# room_sensors.net
KiCad netlist of a schematic drawn in EAGLE
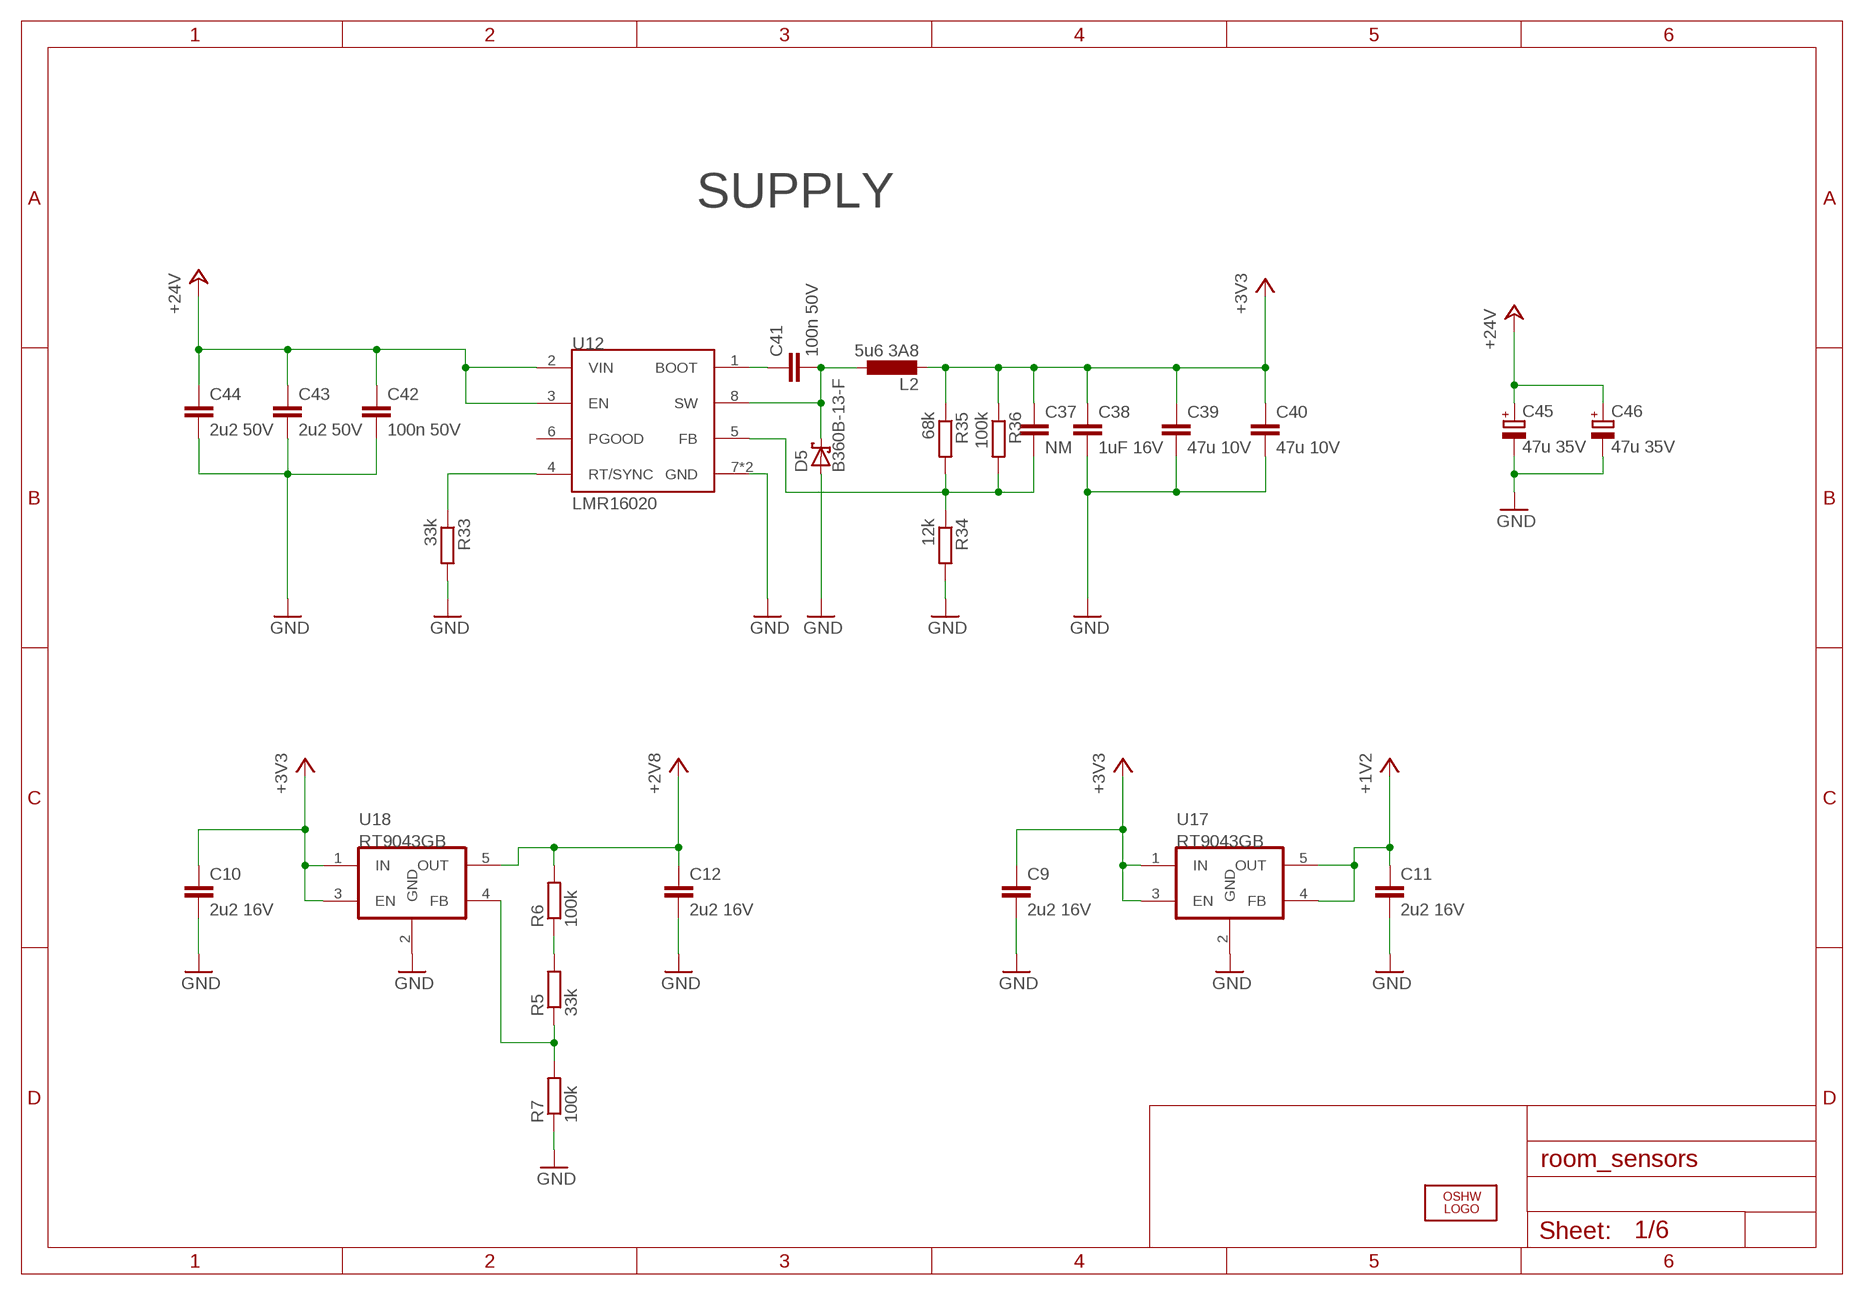
[diagram p0: schematic, sheet 1]
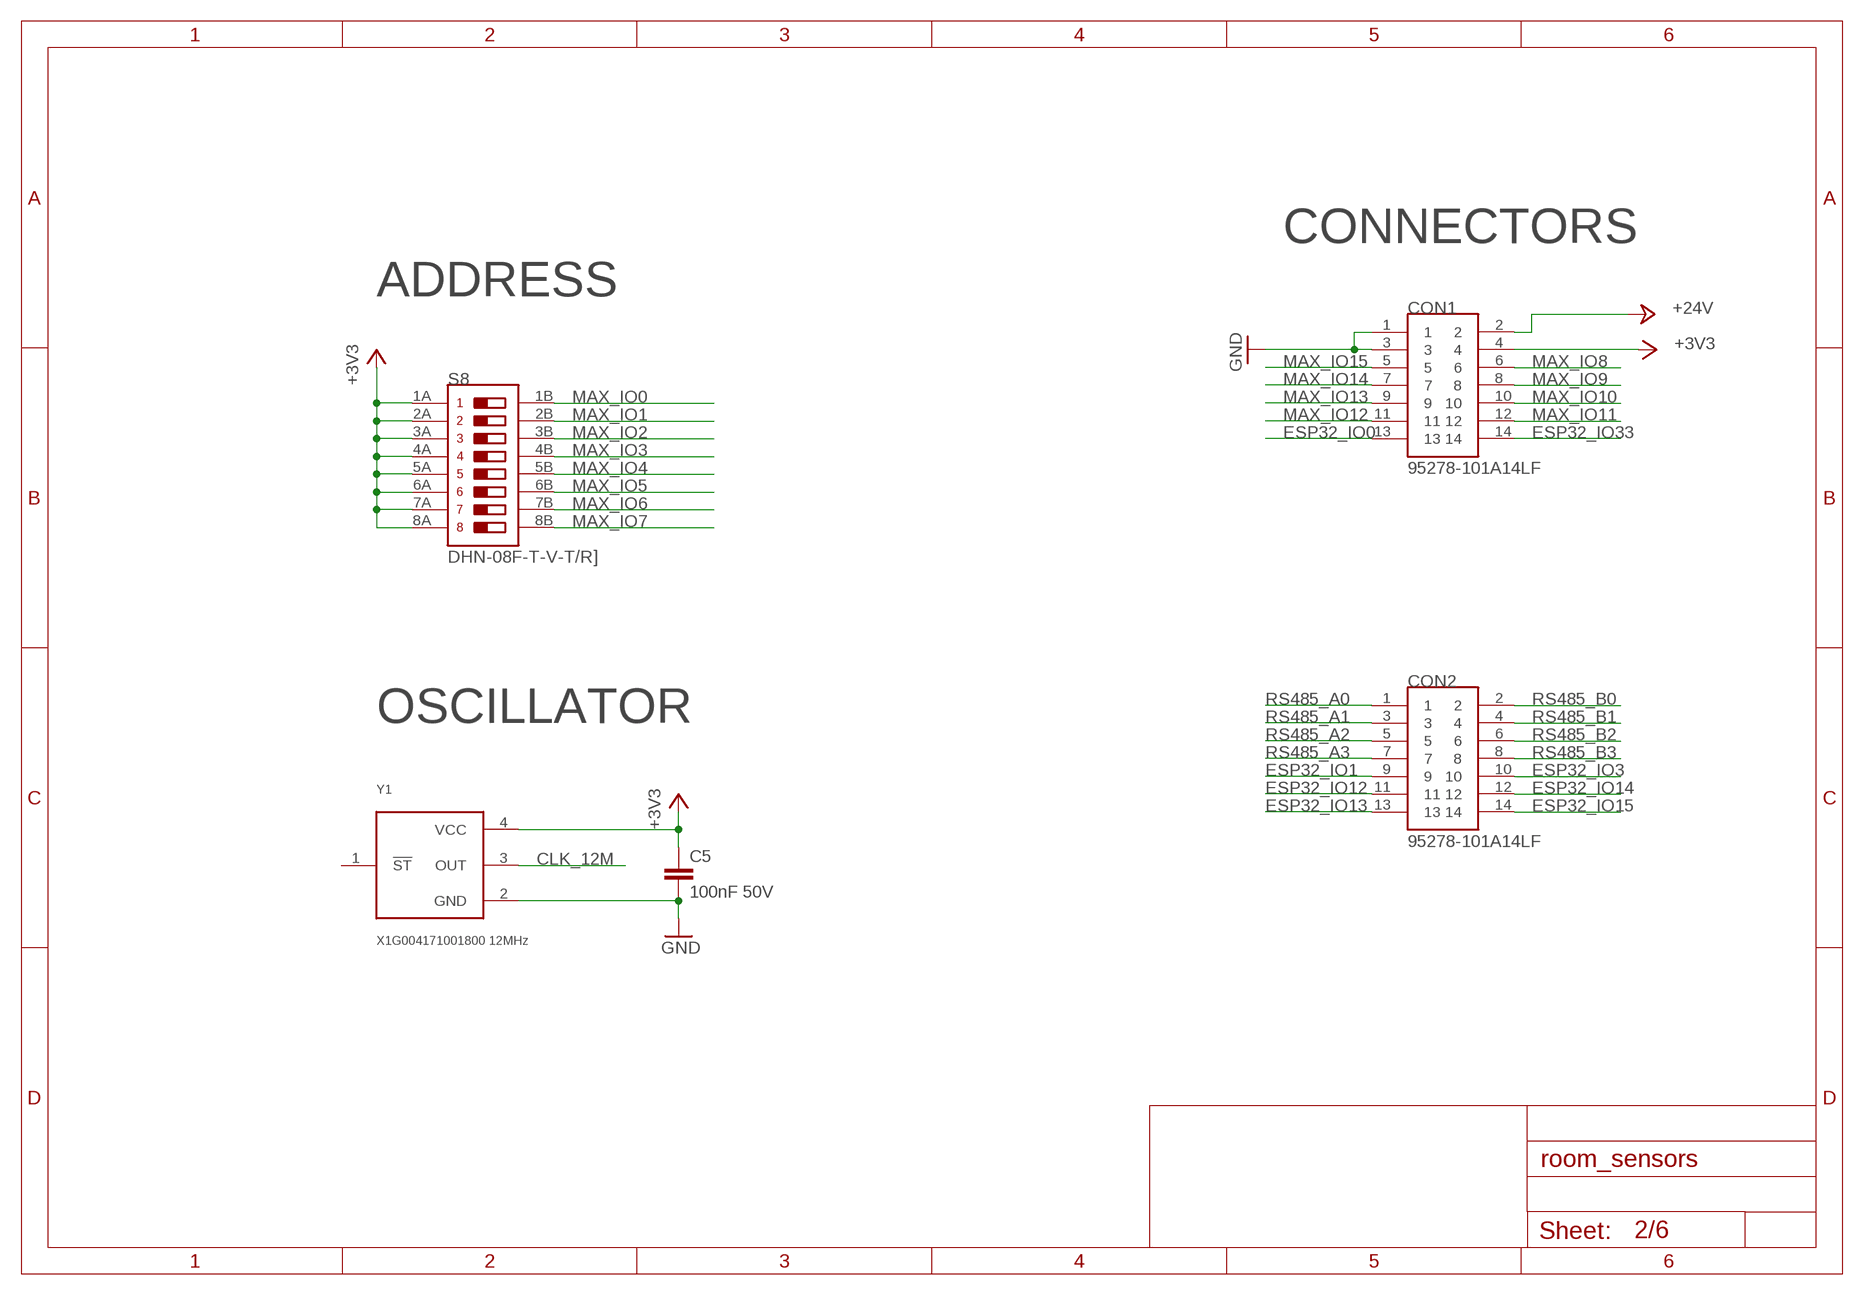
[diagram p1: schematic, sheet 2]
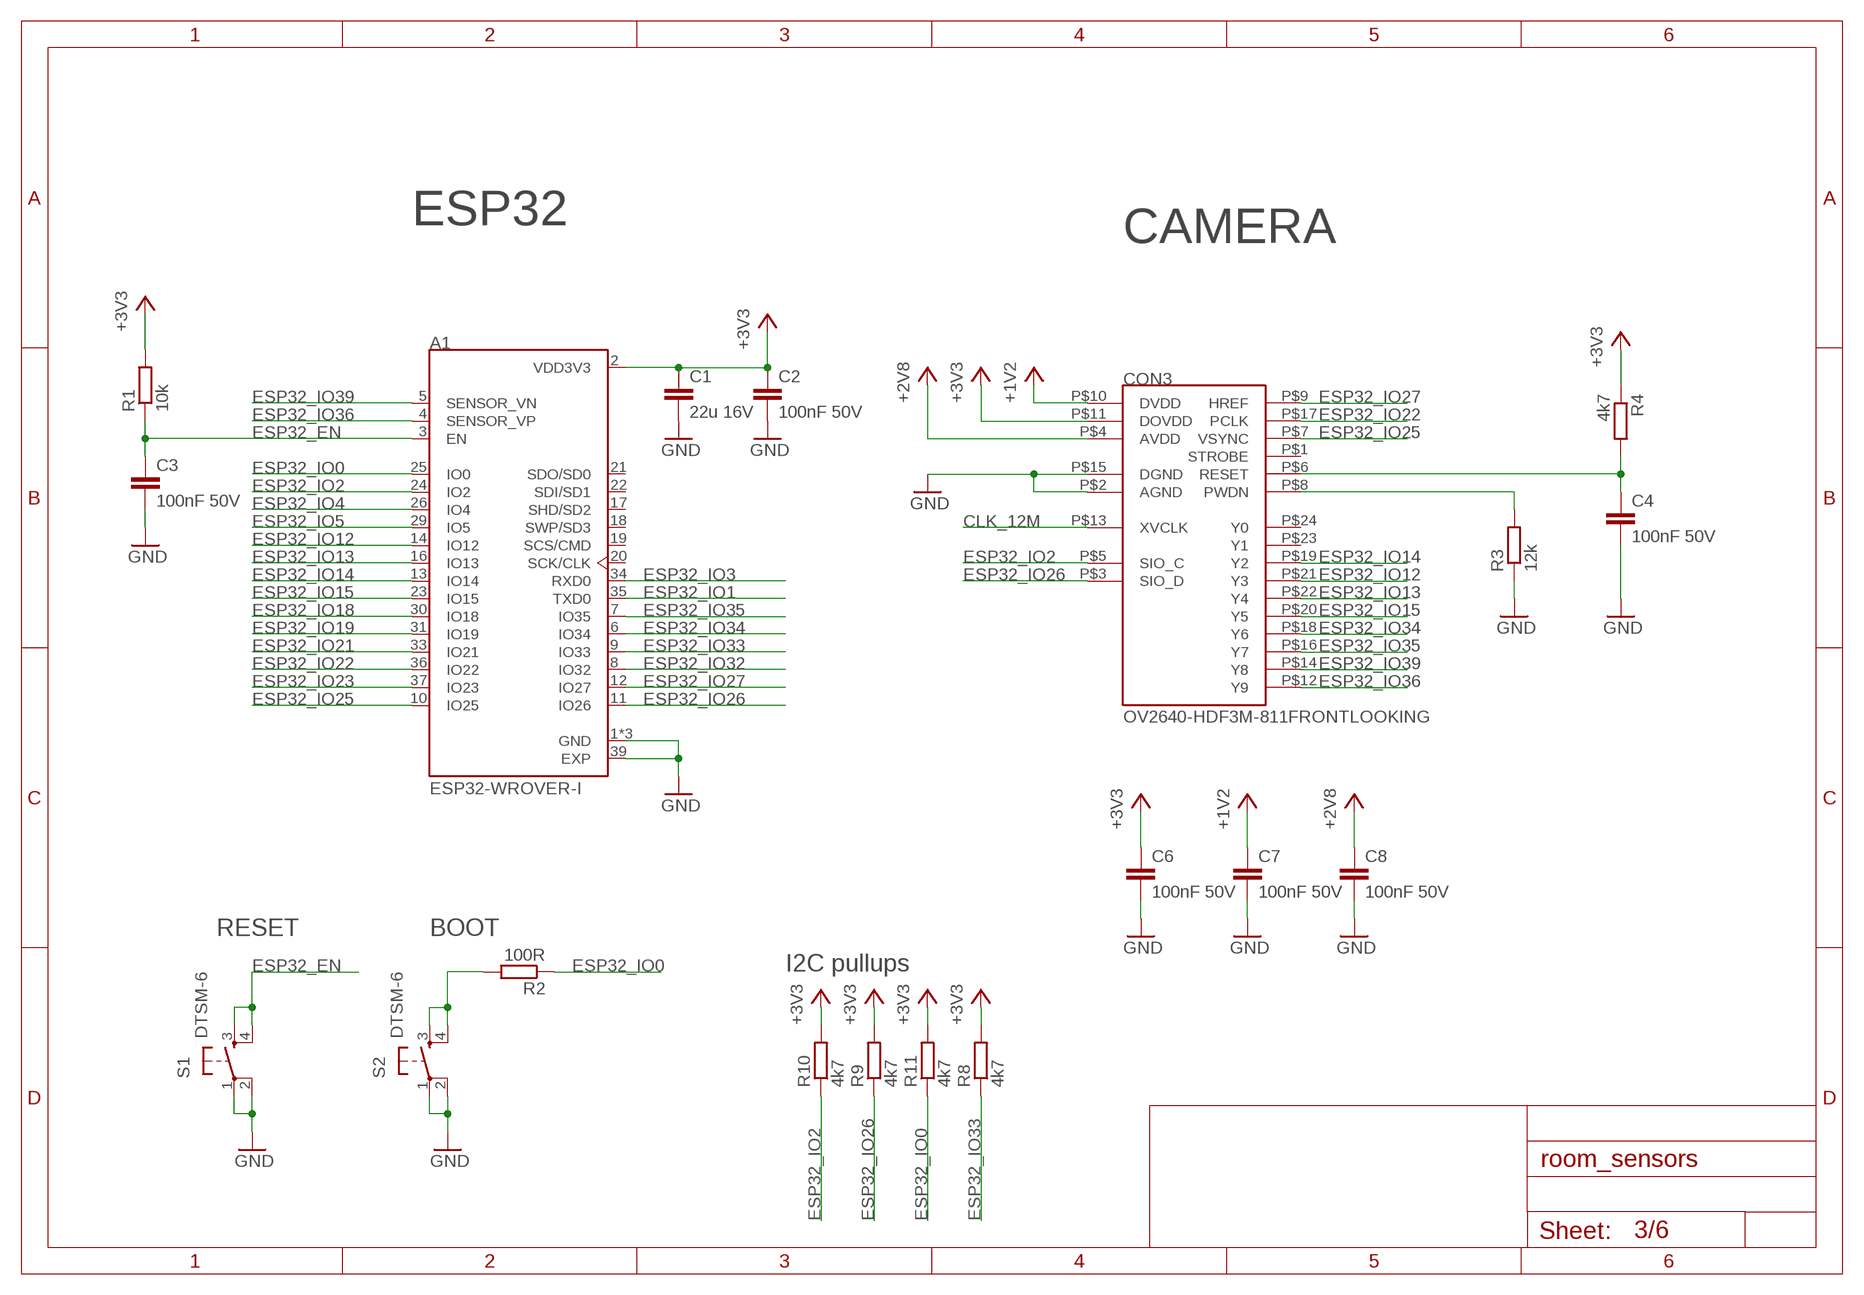
[diagram p2: schematic, sheet 3]
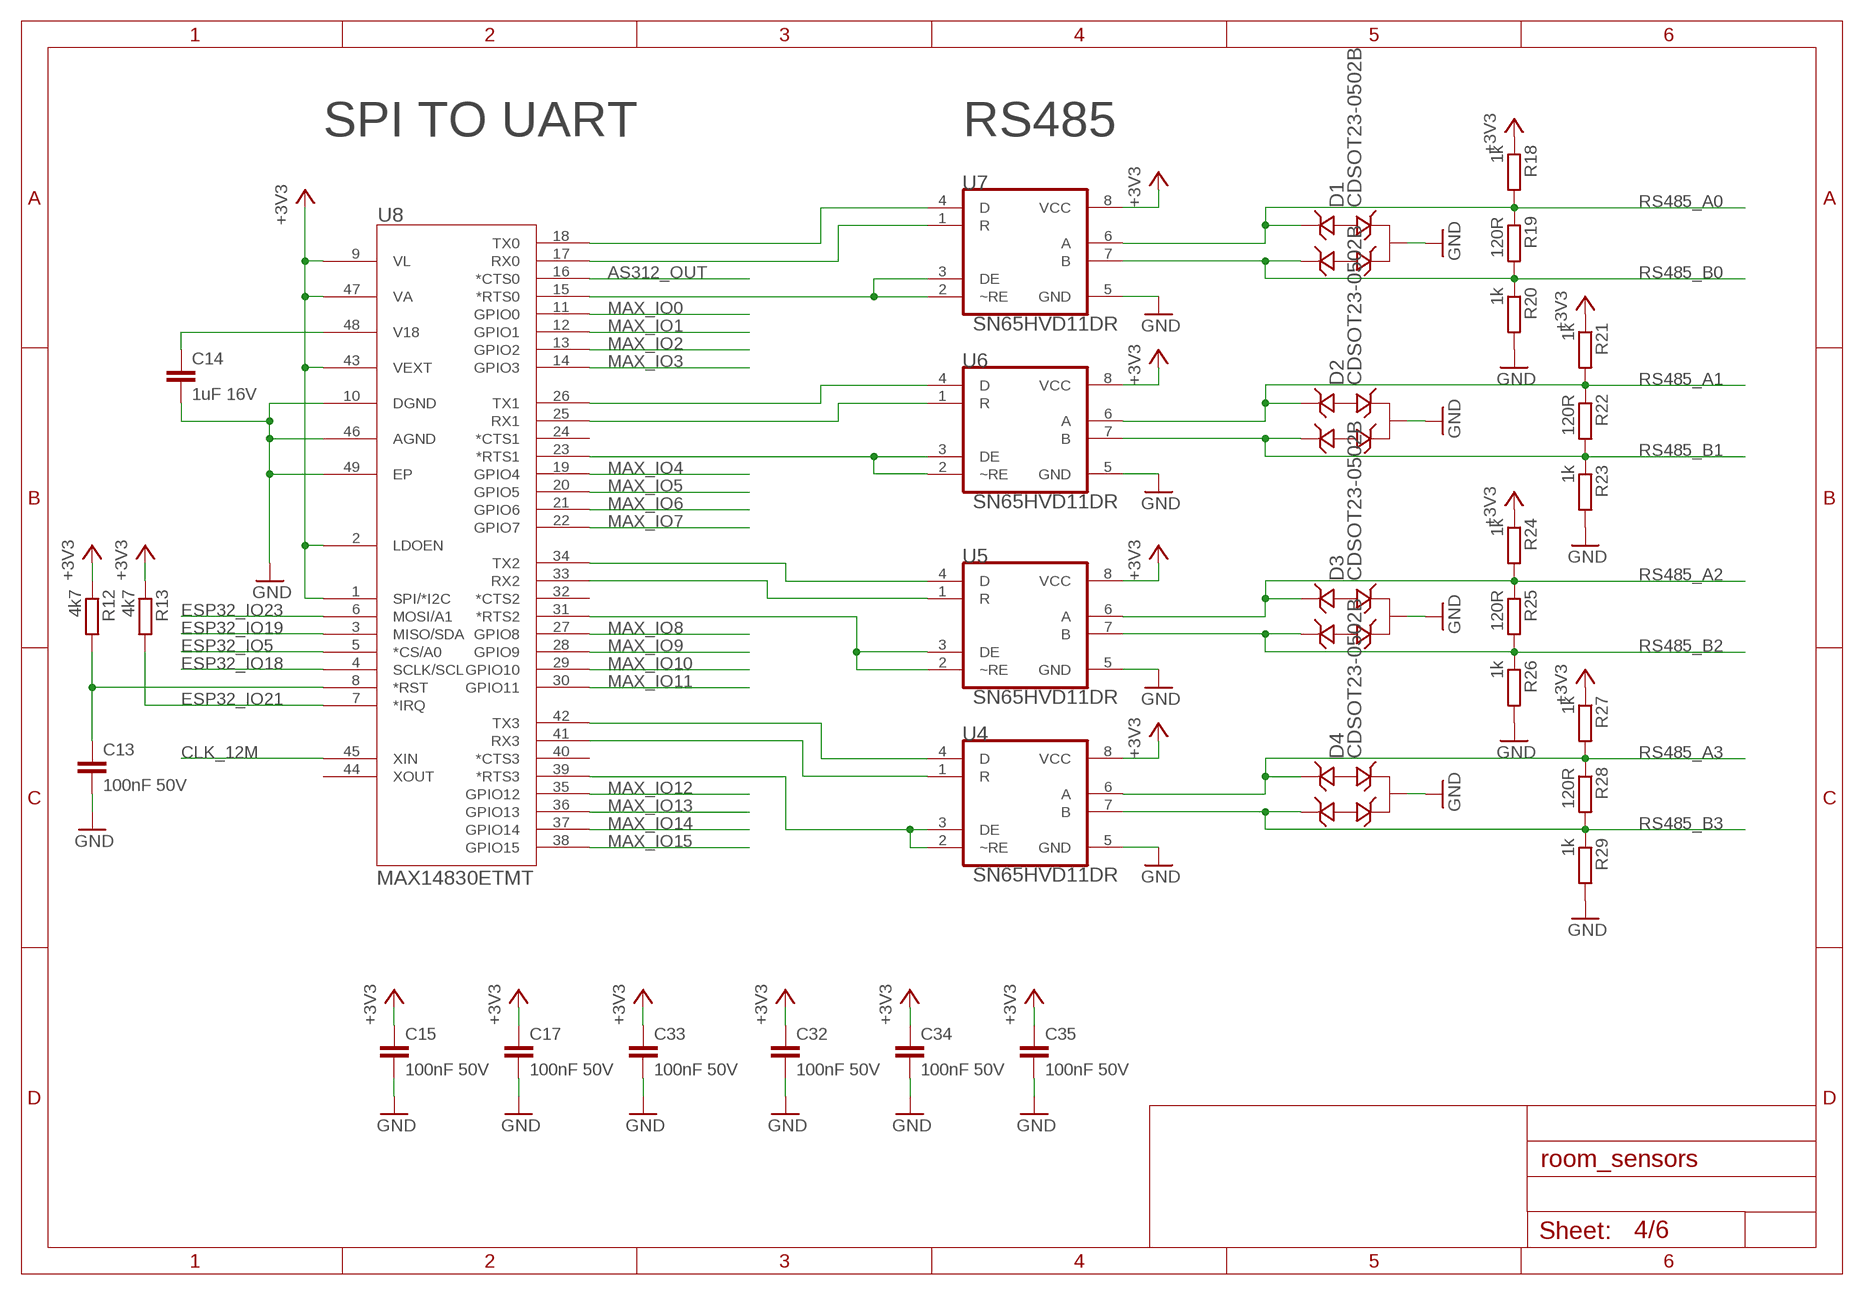
[diagram p3: schematic, sheet 4]
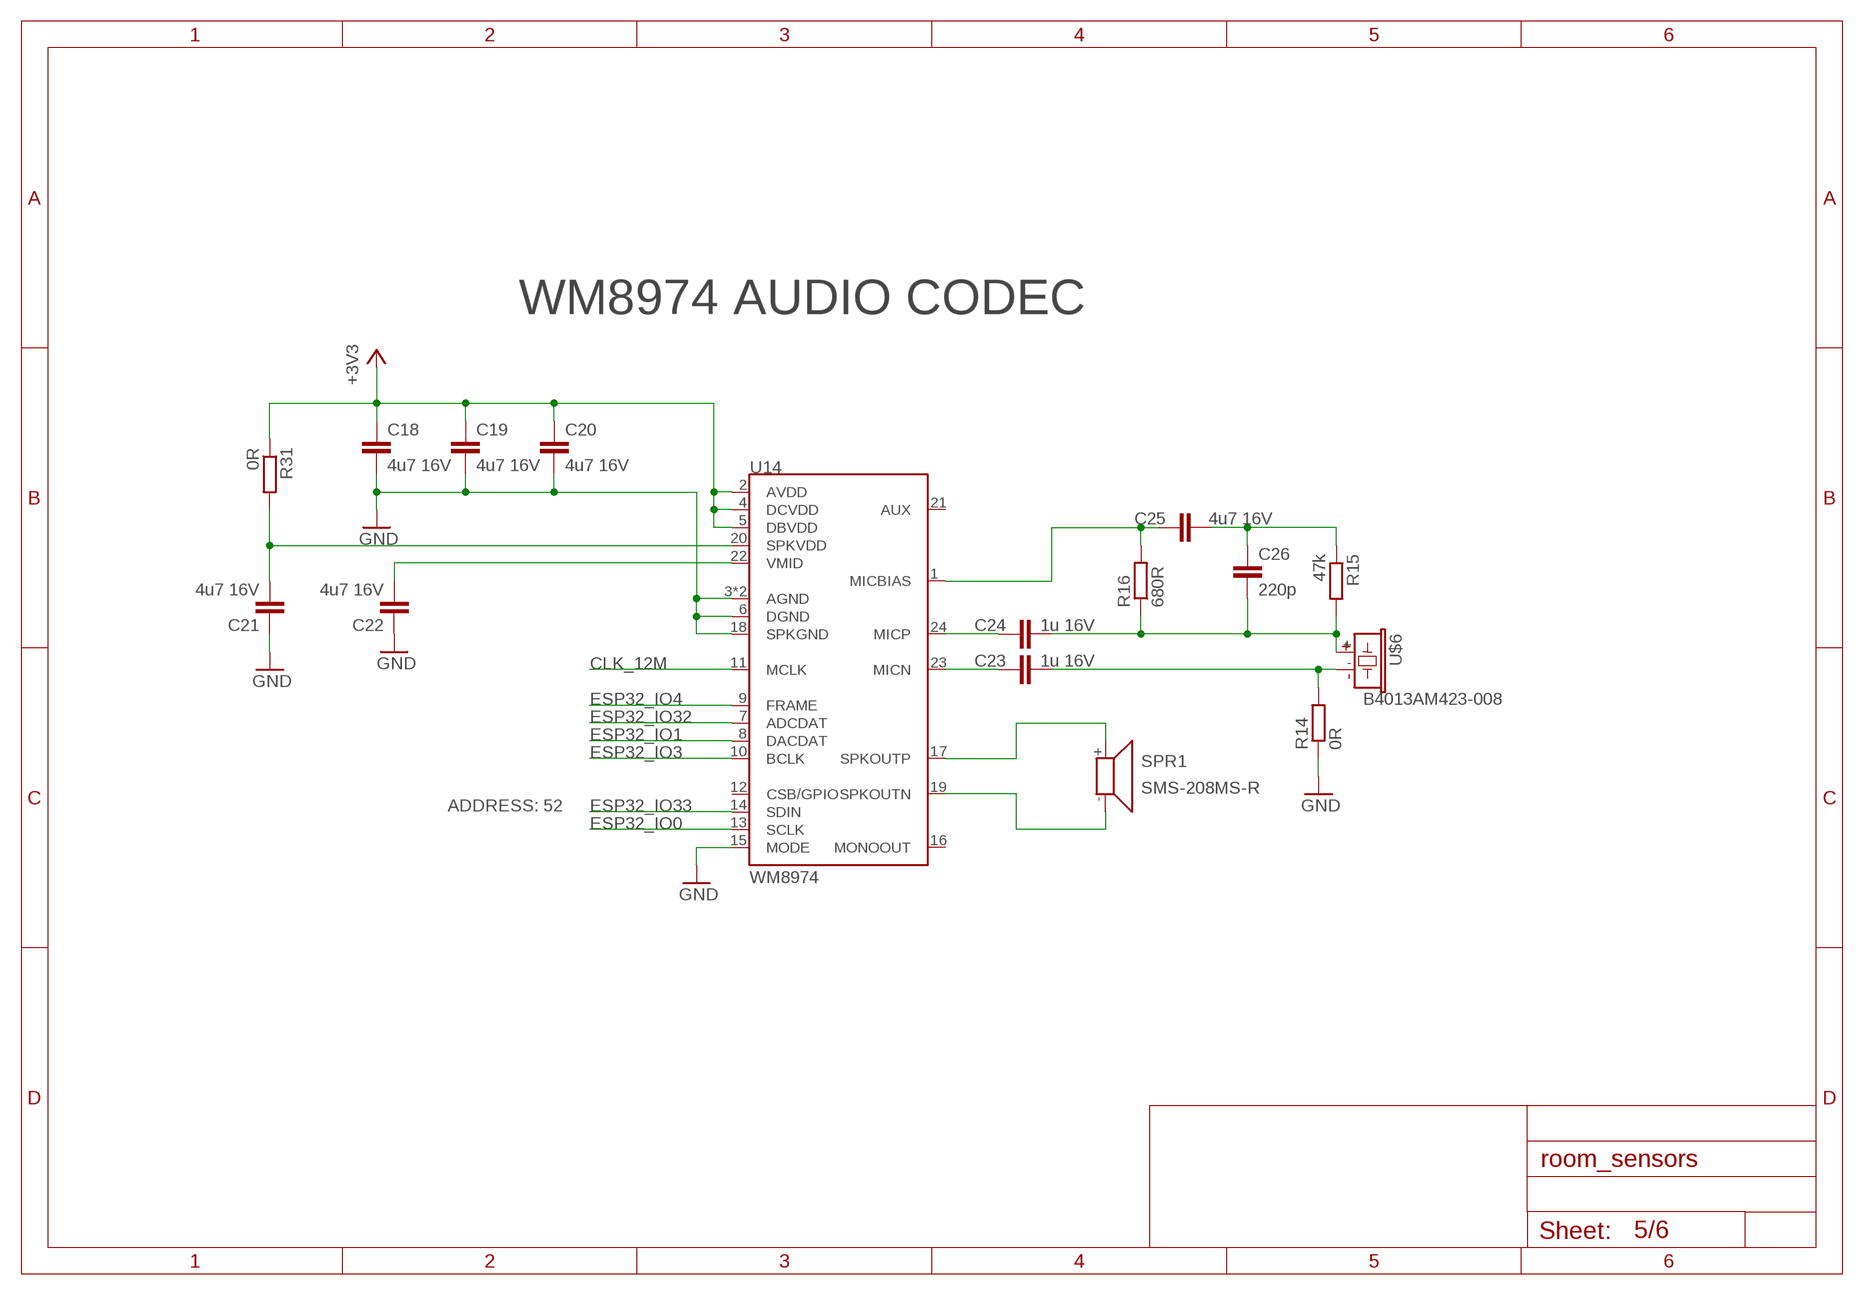
[diagram p4: schematic, sheet 5]
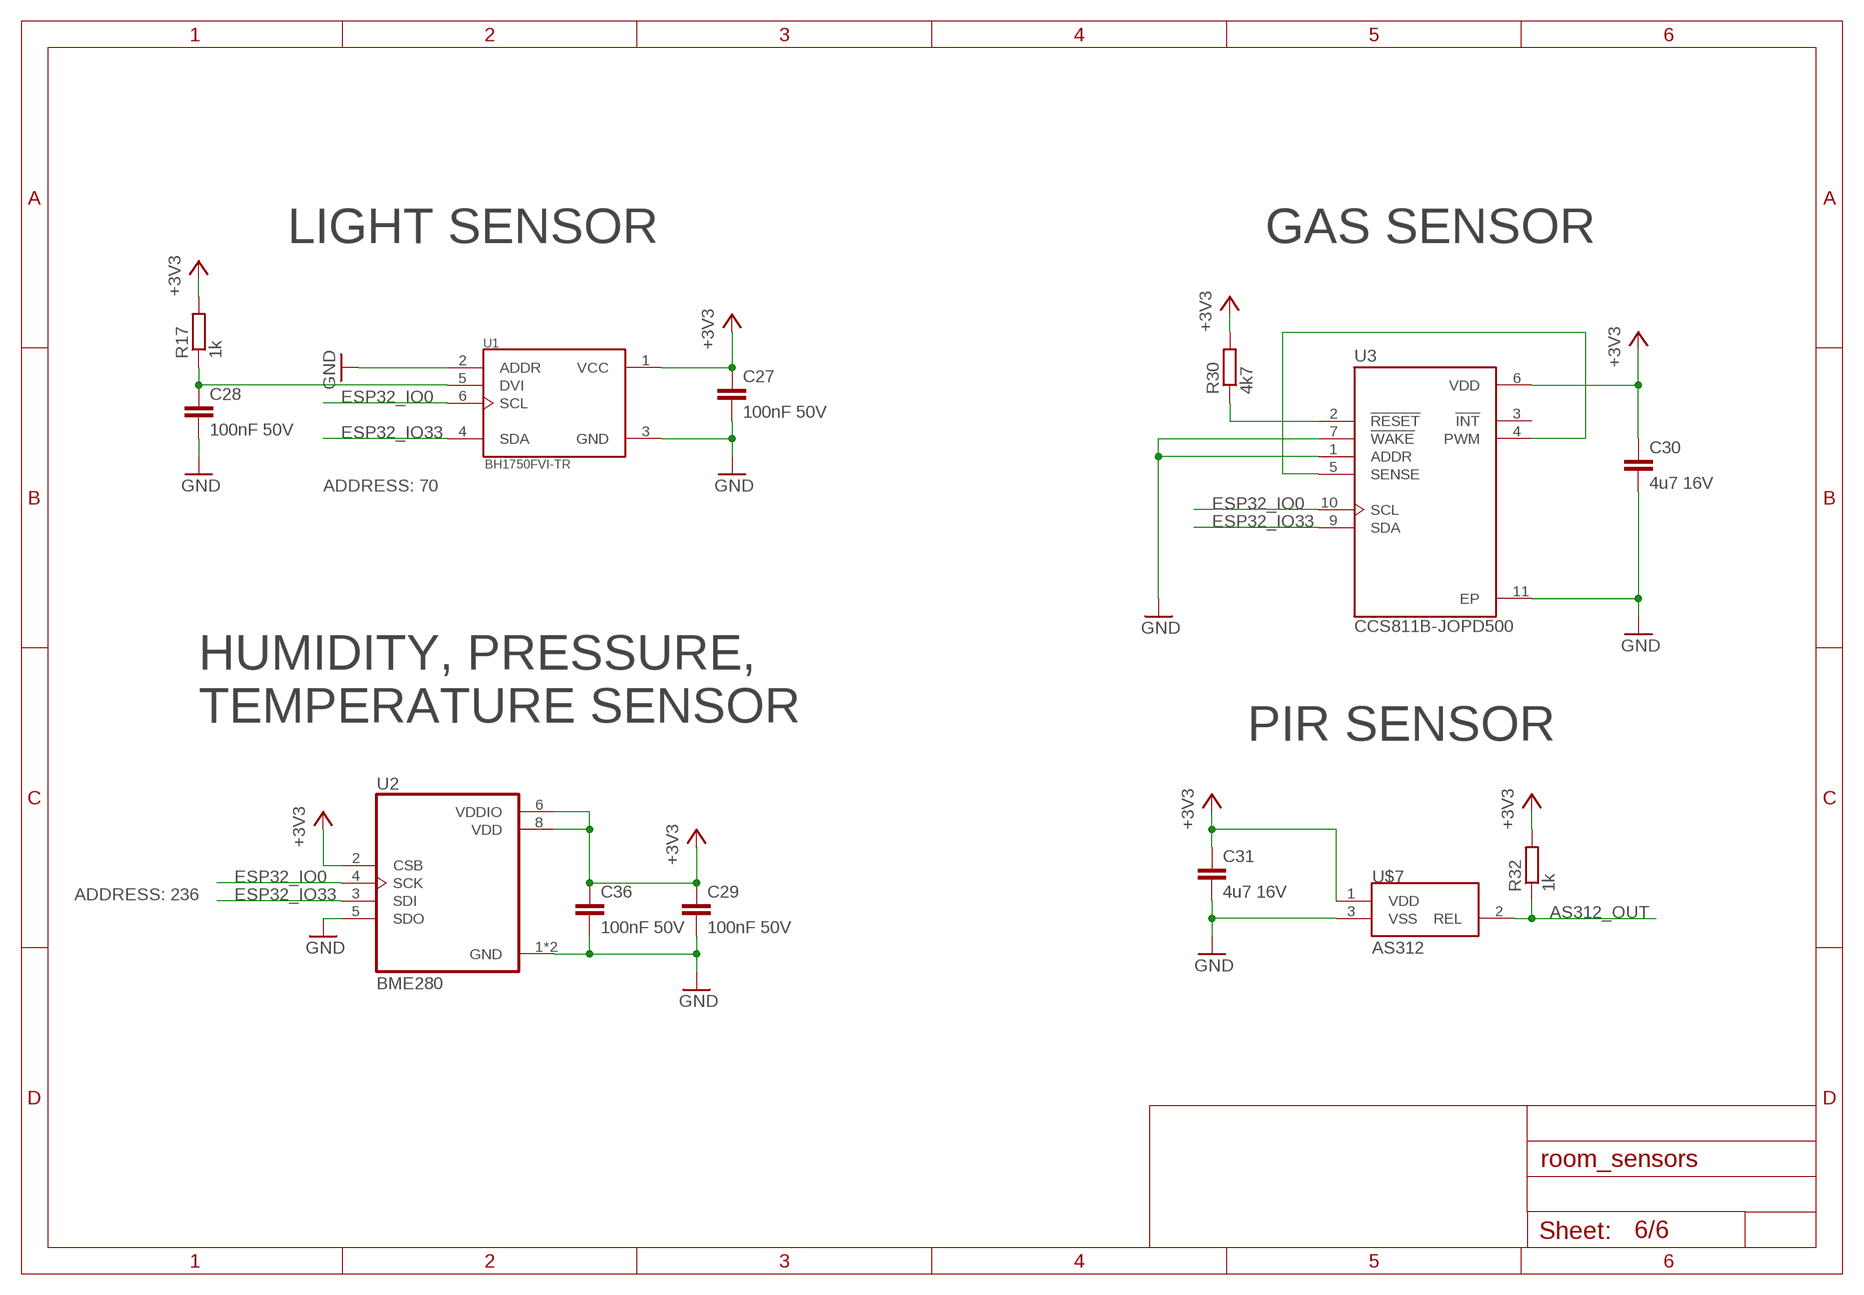
[diagram p5: schematic, sheet 6]

(export (version "E")
  (design (tool "Eeschema 10.0.6"))
  (components
    (comp (ref "C13")
      (value "100nF 50V")
      (footprint "eagle-import:C0805")
      (libsource (lib "eagle-import") (part "C-EUC0805"))
    )
    (comp (ref "C14")
      (value "1uF 16V")
      (footprint "eagle-import:C0805")
      (libsource (lib "eagle-import") (part "C-EUC0805"))
    )
    (comp (ref "C15")
      (value "100nF 50V")
      (footprint "eagle-import:C0805")
      (libsource (lib "eagle-import") (part "C-EUC0805"))
    )
    (comp (ref "C17")
      (value "100nF 50V")
      (footprint "eagle-import:C0805")
      (libsource (lib "eagle-import") (part "C-EUC0805"))
    )
    (comp (ref "C32")
      (value "100nF 50V")
      (footprint "eagle-import:C0805")
      (libsource (lib "eagle-import") (part "C-EUC0805"))
    )
    (comp (ref "C33")
      (value "100nF 50V")
      (footprint "eagle-import:C0805")
      (libsource (lib "eagle-import") (part "C-EUC0805"))
    )
    (comp (ref "C34")
      (value "100nF 50V")
      (footprint "eagle-import:C0805")
      (libsource (lib "eagle-import") (part "C-EUC0805"))
    )
    (comp (ref "C35")
      (value "100nF 50V")
      (footprint "eagle-import:C0805")
      (libsource (lib "eagle-import") (part "C-EUC0805"))
    )
    (comp (ref "D1")
      (value "CDSOT23-0502B")
      (footprint "eagle-import:SOT-23-3")
      (fields (field (name "MF") "Bourns") (field (name "MP") "CDSOT23-SM712"))
      (libsource (lib "eagle-import") (part "CDSOT23-SM712"))
    )
    (comp (ref "D2")
      (value "CDSOT23-0502B")
      (footprint "eagle-import:SOT-23-3")
      (fields (field (name "MF") "Bourns") (field (name "MP") "CDSOT23-SM712"))
      (libsource (lib "eagle-import") (part "CDSOT23-SM712"))
    )
    (comp (ref "D3")
      (value "CDSOT23-0502B")
      (footprint "eagle-import:SOT-23-3")
      (fields (field (name "MF") "Bourns") (field (name "MP") "CDSOT23-SM712"))
      (libsource (lib "eagle-import") (part "CDSOT23-SM712"))
    )
    (comp (ref "D4")
      (value "CDSOT23-0502B")
      (footprint "eagle-import:SOT-23-3")
      (fields (field (name "MF") "Bourns") (field (name "MP") "CDSOT23-SM712"))
      (libsource (lib "eagle-import") (part "CDSOT23-SM712"))
    )
    (comp (ref "R12")
      (value "4k7")
      (footprint "eagle-import:R1206")
      (libsource (lib "eagle-import") (part "R-EU_R1206"))
    )
    (comp (ref "R13")
      (value "4k7")
      (footprint "eagle-import:R1206")
      (libsource (lib "eagle-import") (part "R-EU_R1206"))
    )
    (comp (ref "R18")
      (value "1k")
      (footprint "eagle-import:R1206")
      (libsource (lib "eagle-import") (part "R-EU_R1206"))
    )
    (comp (ref "R19")
      (value "120R")
      (footprint "eagle-import:R1206")
      (libsource (lib "eagle-import") (part "R-EU_R1206"))
    )
    (comp (ref "R20")
      (value "1k")
      (footprint "eagle-import:R1206")
      (libsource (lib "eagle-import") (part "R-EU_R1206"))
    )
    (comp (ref "R21")
      (value "1k")
      (footprint "eagle-import:R1206")
      (libsource (lib "eagle-import") (part "R-EU_R1206"))
    )
    (comp (ref "R22")
      (value "120R")
      (footprint "eagle-import:R1206")
      (libsource (lib "eagle-import") (part "R-EU_R1206"))
    )
    (comp (ref "R23")
      (value "1k")
      (footprint "eagle-import:R1206")
      (libsource (lib "eagle-import") (part "R-EU_R1206"))
    )
    (comp (ref "R24")
      (value "1k")
      (footprint "eagle-import:R1206")
      (libsource (lib "eagle-import") (part "R-EU_R1206"))
    )
    (comp (ref "R25")
      (value "120R")
      (footprint "eagle-import:R1206")
      (libsource (lib "eagle-import") (part "R-EU_R1206"))
    )
    (comp (ref "R26")
      (value "1k")
      (footprint "eagle-import:R1206")
      (libsource (lib "eagle-import") (part "R-EU_R1206"))
    )
    (comp (ref "R27")
      (value "1k")
      (footprint "eagle-import:R1206")
      (libsource (lib "eagle-import") (part "R-EU_R1206"))
    )
    (comp (ref "R28")
      (value "120R")
      (footprint "eagle-import:R1206")
      (libsource (lib "eagle-import") (part "R-EU_R1206"))
    )
    (comp (ref "R29")
      (value "1k")
      (footprint "eagle-import:R1206")
      (libsource (lib "eagle-import") (part "R-EU_R1206"))
    )
    (comp (ref "U4")
      (value "SN65HVD11DR")
      (footprint "eagle-import:SOIC127P600X175-8N")
      (fields (field (name "MF") "Texas Instruments"))
      (libsource (lib "eagle-import") (part "SN65HVD11DR"))
    )
    (comp (ref "U5")
      (value "SN65HVD11DR")
      (footprint "eagle-import:SOIC127P600X175-8N")
      (fields (field (name "MF") "Texas Instruments"))
      (libsource (lib "eagle-import") (part "SN65HVD11DR"))
    )
    (comp (ref "U6")
      (value "SN65HVD11DR")
      (footprint "eagle-import:SOIC127P600X175-8N")
      (fields (field (name "MF") "Texas Instruments"))
      (libsource (lib "eagle-import") (part "SN65HVD11DR"))
    )
    (comp (ref "U7")
      (value "SN65HVD11DR")
      (footprint "eagle-import:SOIC127P600X175-8N")
      (fields (field (name "MF") "Texas Instruments"))
      (libsource (lib "eagle-import") (part "SN65HVD11DR"))
    )
    (comp (ref "U8")
      (value "MAX14830ETMT")
      (footprint "eagle-import:21-0144H_T4877-3")
      (fields (field (name "MF") "Maxim Integrated") (field (name "MP") "MAX14830ETM+"))
      (libsource (lib "eagle-import") (part "MAX14830ETMT"))
    )
    (comp (ref "C5")
      (value "100nF 50V")
      (footprint "eagle-import:C0805")
      (libsource (lib "eagle-import") (part "C-EUC0805"))
    )
    (comp (ref "CON1")
      (value "95278-101A14LF")
      (footprint "eagle-import:95278-101A14LF")
      (libsource (lib "eagle-import") (part "95278-101A14LF"))
    )
    (comp (ref "CON2")
      (value "95278-101A14LF")
      (footprint "eagle-import:95278-101A14LF")
      (libsource (lib "eagle-import") (part "95278-101A14LF"))
    )
    (comp (ref "S8")
      (value "DHN-08F-T-V-T/R]")
      (footprint "eagle-import:DHN-08F-T-V-T_R]")
      (libsource (lib "eagle-import") (part "DHN-08F-T-V-T/R]"))
    )
    (comp (ref "Y1")
      (value "X1G004171001800 12MHz")
      (footprint "eagle-import:OSCCC250X200X80-4N")
      (fields (field (name "MF") "EPSON") (field (name "MP") "X1G0041710033"))
      (libsource (lib "eagle-import") (part "X1G0041710033"))
    )
    (comp (ref "C18")
      (value "4u7 16V")
      (footprint "eagle-import:C0805")
      (libsource (lib "eagle-import") (part "C-EUC0805"))
    )
    (comp (ref "C19")
      (value "4u7 16V")
      (footprint "eagle-import:C0805")
      (libsource (lib "eagle-import") (part "C-EUC0805"))
    )
    (comp (ref "C20")
      (value "4u7 16V")
      (footprint "eagle-import:C0805")
      (libsource (lib "eagle-import") (part "C-EUC0805"))
    )
    (comp (ref "C21")
      (value "4u7 16V")
      (footprint "eagle-import:C0805")
      (libsource (lib "eagle-import") (part "C-EUC0805"))
    )
    (comp (ref "C22")
      (value "4u7 16V")
      (footprint "eagle-import:C0805")
      (libsource (lib "eagle-import") (part "C-EUC0805"))
    )
    (comp (ref "C23")
      (value "1u 16V")
      (footprint "eagle-import:C0805")
      (libsource (lib "eagle-import") (part "C-EUC0805"))
    )
    (comp (ref "C24")
      (value "1u 16V")
      (footprint "eagle-import:C0805")
      (libsource (lib "eagle-import") (part "C-EUC0805"))
    )
    (comp (ref "C25")
      (value "4u7 16V")
      (footprint "eagle-import:C0805")
      (libsource (lib "eagle-import") (part "C-EUC0805"))
    )
    (comp (ref "C26")
      (value "220p")
      (footprint "eagle-import:C0805")
      (libsource (lib "eagle-import") (part "C-EUC0805"))
    )
    (comp (ref "R14")
      (value "0R")
      (footprint "eagle-import:R1206")
      (libsource (lib "eagle-import") (part "R-EU_R1206"))
    )
    (comp (ref "R15")
      (value "47k")
      (footprint "eagle-import:R1206")
      (libsource (lib "eagle-import") (part "R-EU_R1206"))
    )
    (comp (ref "R16")
      (value "680R")
      (footprint "eagle-import:R1206")
      (libsource (lib "eagle-import") (part "R-EU_R1206"))
    )
    (comp (ref "R31")
      (value "0R")
      (footprint "eagle-import:R0603")
      (libsource (lib "eagle-import") (part "R-EU_R0603"))
    )
    (comp (ref "SPR1")
      (value "SMS-208MS-R")
      (footprint "eagle-import:SMS-2008MS-R")
      (libsource (lib "eagle-import") (part "SMS-208MS-R"))
    )
    (comp (ref "U$6")
      (value "B4013AM423-008")
      (footprint "eagle-import:MIC")
      (libsource (lib "eagle-import") (part "B4013AM423-008"))
    )
    (comp (ref "U14")
      (value "WM8974")
      (footprint "eagle-import:QFN-24_ALT2")
      (libsource (lib "eagle-import") (part "WM8974"))
    )
    (comp (ref "C9")
      (value "2u2 16V")
      (footprint "eagle-import:C1206")
      (libsource (lib "eagle-import") (part "C-EUC1206"))
    )
    (comp (ref "C10")
      (value "2u2 16V")
      (footprint "eagle-import:C1206")
      (libsource (lib "eagle-import") (part "C-EUC1206"))
    )
    (comp (ref "C11")
      (value "2u2 16V")
      (footprint "eagle-import:C1206")
      (libsource (lib "eagle-import") (part "C-EUC1206"))
    )
    (comp (ref "C12")
      (value "2u2 16V")
      (footprint "eagle-import:C1206")
      (libsource (lib "eagle-import") (part "C-EUC1206"))
    )
    (comp (ref "C37")
      (value "NM")
      (footprint "eagle-import:C0805")
      (libsource (lib "eagle-import") (part "C-EUC0805"))
    )
    (comp (ref "C38")
      (value "1uF 16V")
      (footprint "eagle-import:C0805")
      (libsource (lib "eagle-import") (part "C-EUC0805"))
    )
    (comp (ref "C39")
      (value "47u 10V")
      (footprint "eagle-import:C1210")
      (libsource (lib "eagle-import") (part "C-EUC1210"))
    )
    (comp (ref "C40")
      (value "47u 10V")
      (footprint "eagle-import:C1210")
      (libsource (lib "eagle-import") (part "C-EUC1210"))
    )
    (comp (ref "C41")
      (value "100n 50V")
      (footprint "eagle-import:C1206")
      (libsource (lib "eagle-import") (part "C-EUC1206"))
    )
    (comp (ref "C42")
      (value "100n 50V")
      (footprint "eagle-import:C1206")
      (libsource (lib "eagle-import") (part "C-EUC1206"))
    )
    (comp (ref "C43")
      (value "2u2 50V")
      (footprint "eagle-import:C1206")
      (libsource (lib "eagle-import") (part "C-EUC1206"))
    )
    (comp (ref "C44")
      (value "2u2 50V")
      (footprint "eagle-import:C1206")
      (libsource (lib "eagle-import") (part "C-EUC1206"))
    )
    (comp (ref "C45")
      (value "47u 35V")
      (footprint "eagle-import:UD-5X5,8_NICHICON")
      (libsource (lib "eagle-import") (part "CPOL-EUUD-5X5,8"))
    )
    (comp (ref "C46")
      (value "47u 35V")
      (footprint "eagle-import:UD-5X5,8_NICHICON")
      (libsource (lib "eagle-import") (part "CPOL-EUUD-5X5,8"))
    )
    (comp (ref "D5")
      (value "B360B-13-F")
      (footprint "eagle-import:SMB")
      (libsource (lib "eagle-import") (part "MBRS130LT3"))
    )
    (comp (ref "L2")
      (value "5u6 3A8")
      (footprint "eagle-import:SLF10145T-150M2R2-PF")
      (libsource (lib "eagle-import") (part "SLF10145T-150M2R2-PF"))
    )
    (comp (ref "LOGO1")
      (value "OSHW_LOGO_FILLX0350-NT")
      (footprint "eagle-import:OSHW_FILLX350_NOTEXT")
      (libsource (lib "eagle-import") (part "OSHW_LOGO_FILLX0350-NT"))
    )
    (comp (ref "R5")
      (value "33k")
      (footprint "eagle-import:R1206")
      (libsource (lib "eagle-import") (part "R-EU_R1206"))
    )
    (comp (ref "R6")
      (value "100k")
      (footprint "eagle-import:R1206")
      (libsource (lib "eagle-import") (part "R-EU_R1206"))
    )
    (comp (ref "R7")
      (value "100k")
      (footprint "eagle-import:R1206")
      (libsource (lib "eagle-import") (part "R-EU_R1206"))
    )
    (comp (ref "R33")
      (value "33k")
      (footprint "eagle-import:R1206")
      (libsource (lib "eagle-import") (part "R-EU_R1206"))
    )
    (comp (ref "R34")
      (value "12k")
      (footprint "eagle-import:R1206")
      (libsource (lib "eagle-import") (part "R-EU_R1206"))
    )
    (comp (ref "R35")
      (value "68k")
      (footprint "eagle-import:R1206")
      (libsource (lib "eagle-import") (part "R-EU_R1206"))
    )
    (comp (ref "R36")
      (value "100k")
      (footprint "eagle-import:R1206")
      (libsource (lib "eagle-import") (part "R-EU_R1206"))
    )
    (comp (ref "U12")
      (value "LMR16020")
      (footprint "eagle-import:SOIC127P600X170-8N")
      (libsource (lib "eagle-import") (part "LMR16020"))
    )
    (comp (ref "U17")
      (value "RT9043GB")
      (footprint "eagle-import:SOP95P275X110-5N")
      (libsource (lib "eagle-import") (part "RT9043GB"))
    )
    (comp (ref "U18")
      (value "RT9043GB")
      (footprint "eagle-import:SOP95P275X110-5N")
      (libsource (lib "eagle-import") (part "RT9043GB"))
    )
    (comp (ref "A1")
      (value "ESP32-WROVER-I")
      (footprint "eagle-import:XCVR_ESP32-WROVER-I")
      (fields (field (name "MF") "Espressif Systems"))
      (libsource (lib "eagle-import") (part "ESP32-WROVER-I"))
    )
    (comp (ref "C1")
      (value "22u 16V")
      (footprint "eagle-import:C1210")
      (libsource (lib "eagle-import") (part "C-EUC1210"))
    )
    (comp (ref "C2")
      (value "100nF 50V")
      (footprint "eagle-import:C0805")
      (libsource (lib "eagle-import") (part "C-EUC0805"))
    )
    (comp (ref "C3")
      (value "100nF 50V")
      (footprint "eagle-import:C0805")
      (libsource (lib "eagle-import") (part "C-EUC0805"))
    )
    (comp (ref "C4")
      (value "100nF 50V")
      (footprint "eagle-import:C0805")
      (libsource (lib "eagle-import") (part "C-EUC0805"))
    )
    (comp (ref "C6")
      (value "100nF 50V")
      (footprint "eagle-import:C0805")
      (libsource (lib "eagle-import") (part "C-EUC0805"))
    )
    (comp (ref "C7")
      (value "100nF 50V")
      (footprint "eagle-import:C0805")
      (libsource (lib "eagle-import") (part "C-EUC0805"))
    )
    (comp (ref "C8")
      (value "100nF 50V")
      (footprint "eagle-import:C0805")
      (libsource (lib "eagle-import") (part "C-EUC0805"))
    )
    (comp (ref "CON3")
      (value "OV2640-HDF3M-811FRONTLOOKING")
      (footprint "eagle-import:FH34SRJ-24S-0.5SH(50)")
      (libsource (lib "eagle-import") (part "OV2640-HDF3M-811FRONTLOOKING"))
    )
    (comp (ref "R1")
      (value "10k")
      (footprint "eagle-import:R1206")
      (libsource (lib "eagle-import") (part "R-EU_R1206"))
    )
    (comp (ref "R2")
      (value "100R")
      (footprint "eagle-import:R1206")
      (libsource (lib "eagle-import") (part "R-EU_R1206"))
    )
    (comp (ref "R3")
      (value "12k")
      (footprint "eagle-import:R1206")
      (libsource (lib "eagle-import") (part "R-EU_R1206"))
    )
    (comp (ref "R4")
      (value "4k7")
      (footprint "eagle-import:R1206")
      (libsource (lib "eagle-import") (part "R-EU_R1206"))
    )
    (comp (ref "R8")
      (value "4k7")
      (footprint "eagle-import:R1206")
      (libsource (lib "eagle-import") (part "R-EU_R1206"))
    )
    (comp (ref "R9")
      (value "4k7")
      (footprint "eagle-import:R1206")
      (libsource (lib "eagle-import") (part "R-EU_R1206"))
    )
    (comp (ref "R10")
      (value "4k7")
      (footprint "eagle-import:R1206")
      (libsource (lib "eagle-import") (part "R-EU_R1206"))
    )
    (comp (ref "R11")
      (value "4k7")
      (footprint "eagle-import:R1206")
      (libsource (lib "eagle-import") (part "R-EU_R1206"))
    )
    (comp (ref "S1")
      (value "DTSM-6")
      (footprint "eagle-import:DTSM-6")
      (libsource (lib "eagle-import") (part "DTSM-6"))
    )
    (comp (ref "S2")
      (value "DTSM-6")
      (footprint "eagle-import:DTSM-6")
      (libsource (lib "eagle-import") (part "DTSM-6"))
    )
    (comp (ref "C27")
      (value "100nF 50V")
      (footprint "eagle-import:C0805")
      (libsource (lib "eagle-import") (part "C-EUC0805"))
    )
    (comp (ref "C28")
      (value "100nF 50V")
      (footprint "eagle-import:C0805")
      (libsource (lib "eagle-import") (part "C-EUC0805"))
    )
    (comp (ref "C29")
      (value "100nF 50V")
      (footprint "eagle-import:C0805")
      (libsource (lib "eagle-import") (part "C-EUC0805"))
    )
    (comp (ref "C30")
      (value "4u7 16V")
      (footprint "eagle-import:C0805")
      (libsource (lib "eagle-import") (part "C-EUC0805"))
    )
    (comp (ref "C31")
      (value "4u7 16V")
      (footprint "eagle-import:C0805")
      (libsource (lib "eagle-import") (part "C-EUC0805"))
    )
    (comp (ref "C36")
      (value "100nF 50V")
      (footprint "eagle-import:C0805")
      (libsource (lib "eagle-import") (part "C-EUC0805"))
    )
    (comp (ref "R17")
      (value "1k")
      (footprint "eagle-import:R1206")
      (libsource (lib "eagle-import") (part "R-EU_R1206"))
    )
    (comp (ref "R30")
      (value "4k7")
      (footprint "eagle-import:R1206")
      (libsource (lib "eagle-import") (part "R-EU_R1206"))
    )
    (comp (ref "R32")
      (value "1k")
      (footprint "eagle-import:R1206")
      (libsource (lib "eagle-import") (part "R-EU_R1206"))
    )
    (comp (ref "U$7")
      (value "AS312")
      (footprint "eagle-import:TO-39")
      (libsource (lib "eagle-import") (part "AS312"))
    )
    (comp (ref "U1")
      (value "BH1750FVI-TR")
      (footprint "eagle-import:SOTFL50P300X75-6N")
      (fields (field (name "MF") "Rohm"))
      (libsource (lib "eagle-import") (part "BH1750FVI-TR"))
    )
    (comp (ref "U2")
      (value "BME280")
      (footprint "eagle-import:PSON65P250X250X100-8N")
      (fields (field (name "MF") "Bosch"))
      (libsource (lib "eagle-import") (part "BME280"))
    )
    (comp (ref "U3")
      (value "CCS811B-JOPD500")
      (footprint "eagle-import:SON60P400X270X110-11N")
      (fields (field (name "MF") "ams"))
      (libsource (lib "eagle-import") (part "CCS811B-JOPD500"))
    )
  )
  (nets
    (net (code "1") (name "+1V2") (class "Default")
      (node (ref "C11") (pin "1") (pinfunction "1_1") (pintype "passive"))
      (node (ref "C7") (pin "1") (pinfunction "1_1") (pintype "passive"))
      (node (ref "CON3") (pin "P$10") (pinfunction "DVDD_P$10") (pintype "power_in"))
      (node (ref "U17") (pin "4") (pinfunction "FB_4") (pintype "power_in"))
      (node (ref "U17") (pin "5") (pinfunction "OUT_5") (pintype "power_in"))
    )
    (net (code "2") (name "+2V8") (class "Default")
      (node (ref "C12") (pin "1") (pinfunction "1_1") (pintype "passive"))
      (node (ref "C8") (pin "1") (pinfunction "1_1") (pintype "passive"))
      (node (ref "CON3") (pin "P$4") (pinfunction "AVDD_P$4") (pintype "power_in"))
      (node (ref "R6") (pin "2") (pinfunction "2_2") (pintype "passive"))
      (node (ref "U18") (pin "5") (pinfunction "OUT_5") (pintype "power_in"))
    )
    (net (code "3") (name "+3V3") (class "Default")
      (node (ref "A1") (pin "2") (pinfunction "VDD3V3_2") (pintype "power_in"))
      (node (ref "C1") (pin "1") (pinfunction "1_1") (pintype "passive"))
      (node (ref "C10") (pin "1") (pinfunction "1_1") (pintype "passive"))
      (node (ref "C15") (pin "1") (pinfunction "1_1") (pintype "passive"))
      (node (ref "C17") (pin "1") (pinfunction "1_1") (pintype "passive"))
      (node (ref "C18") (pin "1") (pinfunction "1_1") (pintype "passive"))
      (node (ref "C19") (pin "1") (pinfunction "1_1") (pintype "passive"))
      (node (ref "C2") (pin "1") (pinfunction "1_1") (pintype "passive"))
      (node (ref "C20") (pin "1") (pinfunction "1_1") (pintype "passive"))
      (node (ref "C27") (pin "1") (pinfunction "1_1") (pintype "passive"))
      (node (ref "C29") (pin "1") (pinfunction "1_1") (pintype "passive"))
      (node (ref "C30") (pin "1") (pinfunction "1_1") (pintype "passive"))
      (node (ref "C31") (pin "1") (pinfunction "1_1") (pintype "passive"))
      (node (ref "C32") (pin "1") (pinfunction "1_1") (pintype "passive"))
      (node (ref "C33") (pin "1") (pinfunction "1_1") (pintype "passive"))
      (node (ref "C34") (pin "1") (pinfunction "1_1") (pintype "passive"))
      (node (ref "C35") (pin "1") (pinfunction "1_1") (pintype "passive"))
      (node (ref "C36") (pin "1") (pinfunction "1_1") (pintype "passive"))
      (node (ref "C37") (pin "1") (pinfunction "1_1") (pintype "passive"))
      (node (ref "C38") (pin "1") (pinfunction "1_1") (pintype "passive"))
      (node (ref "C39") (pin "1") (pinfunction "1_1") (pintype "passive"))
      (node (ref "C40") (pin "1") (pinfunction "1_1") (pintype "passive"))
      (node (ref "C5") (pin "1") (pinfunction "1_1") (pintype "passive"))
      (node (ref "C6") (pin "1") (pinfunction "1_1") (pintype "passive"))
      (node (ref "C9") (pin "1") (pinfunction "1_1") (pintype "passive"))
      (node (ref "CON1") (pin "4") (pinfunction "4_4") (pintype "passive"))
      (node (ref "CON3") (pin "P$11") (pinfunction "DOVDD_P$11") (pintype "power_in"))
      (node (ref "L2") (pin "P$2") (pinfunction "2_P$2") (pintype "passive"))
      (node (ref "R1") (pin "2") (pinfunction "2_2") (pintype "passive"))
      (node (ref "R10") (pin "2") (pinfunction "2_2") (pintype "passive"))
      (node (ref "R11") (pin "2") (pinfunction "2_2") (pintype "passive"))
      (node (ref "R12") (pin "1") (pinfunction "1_1") (pintype "passive"))
      (node (ref "R13") (pin "1") (pinfunction "1_1") (pintype "passive"))
      (node (ref "R17") (pin "2") (pinfunction "2_2") (pintype "passive"))
      (node (ref "R18") (pin "1") (pinfunction "1_1") (pintype "passive"))
      (node (ref "R21") (pin "1") (pinfunction "1_1") (pintype "passive"))
      (node (ref "R24") (pin "1") (pinfunction "1_1") (pintype "passive"))
      (node (ref "R27") (pin "1") (pinfunction "1_1") (pintype "passive"))
      (node (ref "R30") (pin "2") (pinfunction "2_2") (pintype "passive"))
      (node (ref "R31") (pin "1") (pinfunction "1_1") (pintype "passive"))
      (node (ref "R32") (pin "2") (pinfunction "2_2") (pintype "passive"))
      (node (ref "R35") (pin "1") (pinfunction "1_1") (pintype "passive"))
      (node (ref "R36") (pin "1") (pinfunction "1_1") (pintype "passive"))
      (node (ref "R4") (pin "1") (pinfunction "1_1") (pintype "passive"))
      (node (ref "R8") (pin "2") (pinfunction "2_2") (pintype "passive"))
      (node (ref "R9") (pin "2") (pinfunction "2_2") (pintype "passive"))
      (node (ref "S8") (pin "1A") (pinfunction "1A_1A") (pintype "passive"))
      (node (ref "S8") (pin "2A") (pinfunction "2A_2A") (pintype "passive"))
      (node (ref "S8") (pin "3A") (pinfunction "3A_3A") (pintype "passive"))
      (node (ref "S8") (pin "4A") (pinfunction "4A_4A") (pintype "passive"))
      (node (ref "S8") (pin "5A") (pinfunction "5A_5A") (pintype "passive"))
      (node (ref "S8") (pin "6A") (pinfunction "6A_6A") (pintype "passive"))
      (node (ref "S8") (pin "7A") (pinfunction "7A_7A") (pintype "passive"))
      (node (ref "S8") (pin "8A") (pinfunction "8A_8A") (pintype "passive"))
      (node (ref "U$7") (pin "1") (pinfunction "VDD_1") (pintype "power_in"))
      (node (ref "U1") (pin "1") (pinfunction "VCC_1") (pintype "power_in"))
      (node (ref "U14") (pin "2") (pinfunction "AVDD_2") (pintype "power_in"))
      (node (ref "U14") (pin "4") (pinfunction "DCVDD_4") (pintype "power_in"))
      (node (ref "U14") (pin "5") (pinfunction "DBVDD_5") (pintype "power_in"))
      (node (ref "U17") (pin "1") (pinfunction "IN_1") (pintype "power_in"))
      (node (ref "U17") (pin "3") (pinfunction "EN_3") (pintype "power_in"))
      (node (ref "U18") (pin "1") (pinfunction "IN_1") (pintype "power_in"))
      (node (ref "U18") (pin "3") (pinfunction "EN_3") (pintype "power_in"))
      (node (ref "U2") (pin "2") (pinfunction "CSB_2") (pintype "input"))
      (node (ref "U2") (pin "6") (pinfunction "VDDIO_6") (pintype "power_in"))
      (node (ref "U2") (pin "8") (pinfunction "VDD_8") (pintype "power_in"))
      (node (ref "U3") (pin "6") (pinfunction "VDD_6") (pintype "power_in"))
      (node (ref "U4") (pin "8") (pinfunction "VCC_8") (pintype "power_in"))
      (node (ref "U5") (pin "8") (pinfunction "VCC_8") (pintype "power_in"))
      (node (ref "U6") (pin "8") (pinfunction "VCC_8") (pintype "power_in"))
      (node (ref "U7") (pin "8") (pinfunction "VCC_8") (pintype "power_in"))
      (node (ref "U8") (pin "1") (pinfunction "SPI/*I2C_1") (pintype "passive"))
      (node (ref "U8") (pin "2") (pinfunction "LDOEN_2") (pintype "passive"))
      (node (ref "U8") (pin "43") (pinfunction "VEXT_43") (pintype "passive"))
      (node (ref "U8") (pin "47") (pinfunction "VA_47") (pintype "passive"))
      (node (ref "U8") (pin "9") (pinfunction "VL_9") (pintype "power_in"))
      (node (ref "Y1") (pin "4") (pinfunction "VCC_4") (pintype "power_in"))
    )
    (net (code "4") (name "+24V") (class "Default")
      (node (ref "C42") (pin "1") (pinfunction "1_1") (pintype "passive"))
      (node (ref "C43") (pin "1") (pinfunction "1_1") (pintype "passive"))
      (node (ref "C44") (pin "1") (pinfunction "1_1") (pintype "passive"))
      (node (ref "C45") (pin "+") (pinfunction "+_+") (pintype "passive"))
      (node (ref "C46") (pin "+") (pinfunction "+_+") (pintype "passive"))
      (node (ref "CON1") (pin "2") (pinfunction "2_2") (pintype "passive"))
      (node (ref "U12") (pin "2") (pinfunction "VIN_2") (pintype "power_in"))
      (node (ref "U12") (pin "3") (pinfunction "EN_3") (pintype "input"))
    )
    (net (code "5") (name "AS312_OUT") (class "Default")
      (node (ref "R32") (pin "1") (pinfunction "1_1") (pintype "passive"))
      (node (ref "U$7") (pin "2") (pinfunction "REL_2") (pintype "output"))
      (node (ref "U8") (pin "16") (pinfunction "*CTS0_16") (pintype "passive"))
    )
    (net (code "6") (name "CLK_12M") (class "Default")
      (node (ref "CON3") (pin "P$13") (pinfunction "XVCLK_P$13") (pintype "input"))
      (node (ref "U14") (pin "11") (pinfunction "MCLK_11") (pintype "input"))
      (node (ref "U8") (pin "45") (pinfunction "XIN_45") (pintype "passive"))
      (node (ref "Y1") (pin "3") (pinfunction "OUT_3") (pintype "output"))
    )
    (net (code "7") (name "ESP32_EN") (class "Default")
      (node (ref "A1") (pin "3") (pinfunction "EN_3") (pintype "input"))
      (node (ref "C3") (pin "1") (pinfunction "1_1") (pintype "passive"))
      (node (ref "R1") (pin "1") (pinfunction "1_1") (pintype "passive"))
      (node (ref "S1") (pin "3") (pinfunction "3_3") (pintype "passive"))
      (node (ref "S1") (pin "4") (pinfunction "4_4") (pintype "passive"))
    )
    (net (code "8") (name "ESP32_IO0") (class "Default")
      (node (ref "A1") (pin "25") (pinfunction "IO0_25") (pintype "bidirectional"))
      (node (ref "CON1") (pin "13") (pinfunction "13_13") (pintype "passive"))
      (node (ref "R11") (pin "1") (pinfunction "1_1") (pintype "passive"))
      (node (ref "R2") (pin "1") (pinfunction "1_1") (pintype "passive"))
      (node (ref "U1") (pin "6") (pinfunction "SCL_6") (pintype "input"))
      (node (ref "U14") (pin "13") (pinfunction "SCLK_13") (pintype "input"))
      (node (ref "U2") (pin "4") (pinfunction "SCK_4") (pintype "input"))
      (node (ref "U3") (pin "10") (pinfunction "SCL_10") (pintype "input"))
    )
    (net (code "9") (name "ESP32_IO1") (class "Default")
      (node (ref "A1") (pin "35") (pinfunction "TXD0_35") (pintype "bidirectional"))
      (node (ref "CON2") (pin "9") (pinfunction "9_9") (pintype "passive"))
      (node (ref "U14") (pin "8") (pinfunction "DACDAT_8") (pintype "input"))
    )
    (net (code "10") (name "ESP32_IO2") (class "Default")
      (node (ref "A1") (pin "24") (pinfunction "IO2_24") (pintype "bidirectional"))
      (node (ref "CON3") (pin "P$5") (pinfunction "SIO_C_P$5") (pintype "input"))
      (node (ref "R10") (pin "1") (pinfunction "1_1") (pintype "passive"))
    )
    (net (code "11") (name "ESP32_IO3") (class "Default")
      (node (ref "A1") (pin "34") (pinfunction "RXD0_34") (pintype "bidirectional"))
      (node (ref "CON2") (pin "10") (pinfunction "10_10") (pintype "passive"))
      (node (ref "U14") (pin "10") (pinfunction "BCLK_10") (pintype "bidirectional"))
    )
    (net (code "12") (name "ESP32_IO4") (class "Default")
      (node (ref "A1") (pin "26") (pinfunction "IO4_26") (pintype "bidirectional"))
      (node (ref "U14") (pin "9") (pinfunction "FRAME_9") (pintype "bidirectional"))
    )
    (net (code "13") (name "ESP32_IO5") (class "Default")
      (node (ref "A1") (pin "29") (pinfunction "IO5_29") (pintype "bidirectional"))
      (node (ref "U8") (pin "5") (pinfunction "*CS/A0_5") (pintype "passive"))
    )
    (net (code "14") (name "ESP32_IO12") (class "Default")
      (node (ref "A1") (pin "14") (pinfunction "IO12_14") (pintype "bidirectional"))
      (node (ref "CON2") (pin "11") (pinfunction "11_11") (pintype "passive"))
      (node (ref "CON3") (pin "P$21") (pinfunction "Y3_P$21") (pintype "output"))
    )
    (net (code "15") (name "ESP32_IO13") (class "Default")
      (node (ref "A1") (pin "16") (pinfunction "IO13_16") (pintype "bidirectional"))
      (node (ref "CON2") (pin "13") (pinfunction "13_13") (pintype "passive"))
      (node (ref "CON3") (pin "P$22") (pinfunction "Y4_P$22") (pintype "output"))
    )
    (net (code "16") (name "ESP32_IO14") (class "Default")
      (node (ref "A1") (pin "13") (pinfunction "IO14_13") (pintype "bidirectional"))
      (node (ref "CON2") (pin "12") (pinfunction "12_12") (pintype "passive"))
      (node (ref "CON3") (pin "P$19") (pinfunction "Y2_P$19") (pintype "output"))
    )
    (net (code "17") (name "ESP32_IO15") (class "Default")
      (node (ref "A1") (pin "23") (pinfunction "IO15_23") (pintype "bidirectional"))
      (node (ref "CON2") (pin "14") (pinfunction "14_14") (pintype "passive"))
      (node (ref "CON3") (pin "P$20") (pinfunction "Y5_P$20") (pintype "output"))
    )
    (net (code "18") (name "ESP32_IO18") (class "Default")
      (node (ref "A1") (pin "30") (pinfunction "IO18_30") (pintype "bidirectional"))
      (node (ref "U8") (pin "4") (pinfunction "SCLK/SCL_4") (pintype "passive"))
    )
    (net (code "19") (name "ESP32_IO19") (class "Default")
      (node (ref "A1") (pin "31") (pinfunction "IO19_31") (pintype "bidirectional"))
      (node (ref "U8") (pin "3") (pinfunction "MISO/SDA_3") (pintype "passive"))
    )
    (net (code "20") (name "ESP32_IO21") (class "Default")
      (node (ref "A1") (pin "33") (pinfunction "IO21_33") (pintype "bidirectional"))
      (node (ref "R13") (pin "2") (pinfunction "2_2") (pintype "passive"))
      (node (ref "U8") (pin "7") (pinfunction "*IRQ_7") (pintype "passive"))
    )
    (net (code "21") (name "ESP32_IO22") (class "Default")
      (node (ref "A1") (pin "36") (pinfunction "IO22_36") (pintype "bidirectional"))
      (node (ref "CON3") (pin "P$17") (pinfunction "PCLK_P$17") (pintype "output"))
    )
    (net (code "22") (name "ESP32_IO23") (class "Default")
      (node (ref "A1") (pin "37") (pinfunction "IO23_37") (pintype "bidirectional"))
      (node (ref "U8") (pin "6") (pinfunction "MOSI/A1_6") (pintype "passive"))
    )
    (net (code "23") (name "ESP32_IO25") (class "Default")
      (node (ref "A1") (pin "10") (pinfunction "IO25_10") (pintype "bidirectional"))
      (node (ref "CON3") (pin "P$7") (pinfunction "VSYNC_P$7") (pintype "output"))
    )
    (net (code "24") (name "ESP32_IO26") (class "Default")
      (node (ref "A1") (pin "11") (pinfunction "IO26_11") (pintype "bidirectional"))
      (node (ref "CON3") (pin "P$3") (pinfunction "SIO_D_P$3") (pintype "bidirectional"))
      (node (ref "R9") (pin "1") (pinfunction "1_1") (pintype "passive"))
    )
    (net (code "25") (name "ESP32_IO27") (class "Default")
      (node (ref "A1") (pin "12") (pinfunction "IO27_12") (pintype "bidirectional"))
      (node (ref "CON3") (pin "P$9") (pinfunction "HREF_P$9") (pintype "output"))
    )
    (net (code "26") (name "ESP32_IO32") (class "Default")
      (node (ref "A1") (pin "8") (pinfunction "IO32_8") (pintype "bidirectional"))
      (node (ref "U14") (pin "7") (pinfunction "ADCDAT_7") (pintype "output"))
    )
    (net (code "27") (name "ESP32_IO33") (class "Default")
      (node (ref "A1") (pin "9") (pinfunction "IO33_9") (pintype "bidirectional"))
      (node (ref "CON1") (pin "14") (pinfunction "14_14") (pintype "passive"))
      (node (ref "R8") (pin "1") (pinfunction "1_1") (pintype "passive"))
      (node (ref "U1") (pin "4") (pinfunction "SDA_4") (pintype "bidirectional"))
      (node (ref "U14") (pin "14") (pinfunction "SDIN_14") (pintype "bidirectional"))
      (node (ref "U2") (pin "3") (pinfunction "SDI_3") (pintype "bidirectional"))
      (node (ref "U3") (pin "9") (pinfunction "SDA_9") (pintype "bidirectional"))
    )
    (net (code "28") (name "ESP32_IO34") (class "Default")
      (node (ref "A1") (pin "6") (pinfunction "IO34_6") (pintype "input"))
      (node (ref "CON3") (pin "P$18") (pinfunction "Y6_P$18") (pintype "output"))
    )
    (net (code "29") (name "ESP32_IO35") (class "Default")
      (node (ref "A1") (pin "7") (pinfunction "IO35_7") (pintype "input"))
      (node (ref "CON3") (pin "P$16") (pinfunction "Y7_P$16") (pintype "output"))
    )
    (net (code "30") (name "ESP32_IO36") (class "Default")
      (node (ref "A1") (pin "4") (pinfunction "SENSOR_VP_4") (pintype "input"))
      (node (ref "CON3") (pin "P$12") (pinfunction "Y9_P$12") (pintype "output"))
    )
    (net (code "31") (name "ESP32_IO39") (class "Default")
      (node (ref "A1") (pin "5") (pinfunction "SENSOR_VN_5") (pintype "input"))
      (node (ref "CON3") (pin "P$14") (pinfunction "Y8_P$14") (pintype "output"))
    )
    (net (code "32") (name "GND") (class "Default")
      (node (ref "A1") (pin "1") (pinfunction "GND_1") (pintype "power_in"))
      (node (ref "A1") (pin "15") (pinfunction "GND_15") (pintype "power_in"))
      (node (ref "A1") (pin "38") (pinfunction "GND_38") (pintype "power_in"))
      (node (ref "A1") (pin "39") (pinfunction "EXP_39") (pintype "power_in"))
      (node (ref "C1") (pin "2") (pinfunction "2_2") (pintype "passive"))
      (node (ref "C10") (pin "2") (pinfunction "2_2") (pintype "passive"))
      (node (ref "C11") (pin "2") (pinfunction "2_2") (pintype "passive"))
      (node (ref "C12") (pin "2") (pinfunction "2_2") (pintype "passive"))
      (node (ref "C13") (pin "2") (pinfunction "2_2") (pintype "passive"))
      (node (ref "C14") (pin "2") (pinfunction "2_2") (pintype "passive"))
      (node (ref "C15") (pin "2") (pinfunction "2_2") (pintype "passive"))
      (node (ref "C17") (pin "2") (pinfunction "2_2") (pintype "passive"))
      (node (ref "C18") (pin "2") (pinfunction "2_2") (pintype "passive"))
      (node (ref "C19") (pin "2") (pinfunction "2_2") (pintype "passive"))
      (node (ref "C2") (pin "2") (pinfunction "2_2") (pintype "passive"))
      (node (ref "C20") (pin "2") (pinfunction "2_2") (pintype "passive"))
      (node (ref "C21") (pin "1") (pinfunction "1_1") (pintype "passive"))
      (node (ref "C22") (pin "1") (pinfunction "1_1") (pintype "passive"))
      (node (ref "C27") (pin "2") (pinfunction "2_2") (pintype "passive"))
      (node (ref "C28") (pin "2") (pinfunction "2_2") (pintype "passive"))
      (node (ref "C29") (pin "2") (pinfunction "2_2") (pintype "passive"))
      (node (ref "C3") (pin "2") (pinfunction "2_2") (pintype "passive"))
      (node (ref "C30") (pin "2") (pinfunction "2_2") (pintype "passive"))
      (node (ref "C31") (pin "2") (pinfunction "2_2") (pintype "passive"))
      (node (ref "C32") (pin "2") (pinfunction "2_2") (pintype "passive"))
      (node (ref "C33") (pin "2") (pinfunction "2_2") (pintype "passive"))
      (node (ref "C34") (pin "2") (pinfunction "2_2") (pintype "passive"))
      (node (ref "C35") (pin "2") (pinfunction "2_2") (pintype "passive"))
      (node (ref "C36") (pin "2") (pinfunction "2_2") (pintype "passive"))
      (node (ref "C38") (pin "2") (pinfunction "2_2") (pintype "passive"))
      (node (ref "C39") (pin "2") (pinfunction "2_2") (pintype "passive"))
      (node (ref "C4") (pin "2") (pinfunction "2_2") (pintype "passive"))
      (node (ref "C40") (pin "2") (pinfunction "2_2") (pintype "passive"))
      (node (ref "C42") (pin "2") (pinfunction "2_2") (pintype "passive"))
      (node (ref "C43") (pin "2") (pinfunction "2_2") (pintype "passive"))
      (node (ref "C44") (pin "2") (pinfunction "2_2") (pintype "passive"))
      (node (ref "C45") (pin "-") (pinfunction "-_-") (pintype "passive"))
      (node (ref "C46") (pin "-") (pinfunction "-_-") (pintype "passive"))
      (node (ref "C5") (pin "2") (pinfunction "2_2") (pintype "passive"))
      (node (ref "C6") (pin "2") (pinfunction "2_2") (pintype "passive"))
      (node (ref "C7") (pin "2") (pinfunction "2_2") (pintype "passive"))
      (node (ref "C8") (pin "2") (pinfunction "2_2") (pintype "passive"))
      (node (ref "C9") (pin "2") (pinfunction "2_2") (pintype "passive"))
      (node (ref "CON1") (pin "1") (pinfunction "1_1") (pintype "passive"))
      (node (ref "CON1") (pin "3") (pinfunction "3_3") (pintype "passive"))
      (node (ref "CON3") (pin "P$15") (pinfunction "DGND_P$15") (pintype "power_in"))
      (node (ref "CON3") (pin "P$2") (pinfunction "AGND_P$2") (pintype "power_in"))
      (node (ref "D1") (pin "3") (pinfunction "GND_3") (pintype "bidirectional"))
      (node (ref "D2") (pin "3") (pinfunction "GND_3") (pintype "bidirectional"))
      (node (ref "D3") (pin "3") (pinfunction "GND_3") (pintype "bidirectional"))
      (node (ref "D4") (pin "3") (pinfunction "GND_3") (pintype "bidirectional"))
      (node (ref "D5") (pin "A") (pinfunction "A_A") (pintype "passive"))
      (node (ref "R14") (pin "1") (pinfunction "1_1") (pintype "passive"))
      (node (ref "R20") (pin "2") (pinfunction "2_2") (pintype "passive"))
      (node (ref "R23") (pin "2") (pinfunction "2_2") (pintype "passive"))
      (node (ref "R26") (pin "2") (pinfunction "2_2") (pintype "passive"))
      (node (ref "R29") (pin "2") (pinfunction "2_2") (pintype "passive"))
      (node (ref "R3") (pin "1") (pinfunction "1_1") (pintype "passive"))
      (node (ref "R33") (pin "2") (pinfunction "2_2") (pintype "passive"))
      (node (ref "R34") (pin "2") (pinfunction "2_2") (pintype "passive"))
      (node (ref "R7") (pin "1") (pinfunction "1_1") (pintype "passive"))
      (node (ref "S1") (pin "1") (pinfunction "1_1") (pintype "passive"))
      (node (ref "S1") (pin "2") (pinfunction "2_2") (pintype "passive"))
      (node (ref "S2") (pin "1") (pinfunction "1_1") (pintype "passive"))
      (node (ref "S2") (pin "2") (pinfunction "2_2") (pintype "passive"))
      (node (ref "U$7") (pin "3") (pinfunction "VSS_3") (pintype "power_in"))
      (node (ref "U1") (pin "2") (pinfunction "ADDR_2") (pintype "input"))
      (node (ref "U1") (pin "3") (pinfunction "GND_3") (pintype "power_in"))
      (node (ref "U12") (pin "7") (pinfunction "GND_7") (pintype "power_in"))
      (node (ref "U12") (pin "9") (pinfunction "GND_9") (pintype "power_in"))
      (node (ref "U14") (pin "15") (pinfunction "MODE_15") (pintype "input"))
      (node (ref "U14") (pin "18") (pinfunction "SPKGND_18") (pintype "power_in"))
      (node (ref "U14") (pin "3") (pinfunction "AGND_3") (pintype "power_in"))
      (node (ref "U14") (pin "6") (pinfunction "DGND_6") (pintype "power_in"))
      (node (ref "U14") (pin "EP") (pinfunction "AGND_EP") (pintype "power_in"))
      (node (ref "U17") (pin "2") (pinfunction "GND_2") (pintype "power_in"))
      (node (ref "U18") (pin "2") (pinfunction "GND_2") (pintype "power_in"))
      (node (ref "U2") (pin "1") (pinfunction "GND_1") (pintype "power_in"))
      (node (ref "U2") (pin "5") (pinfunction "SDO_5") (pintype "bidirectional"))
      (node (ref "U2") (pin "7") (pinfunction "GND_7") (pintype "power_in"))
      (node (ref "U3") (pin "1") (pinfunction "ADDR_1") (pintype "input"))
      (node (ref "U3") (pin "11") (pinfunction "EP_11") (pintype "power_in"))
      (node (ref "U3") (pin "7") (pinfunction "~{WAKE}_7") (pintype "input"))
      (node (ref "U4") (pin "5") (pinfunction "GND_5") (pintype "passive"))
      (node (ref "U5") (pin "5") (pinfunction "GND_5") (pintype "passive"))
      (node (ref "U6") (pin "5") (pinfunction "GND_5") (pintype "passive"))
      (node (ref "U7") (pin "5") (pinfunction "GND_5") (pintype "passive"))
      (node (ref "U8") (pin "10") (pinfunction "DGND_10") (pintype "power_in"))
      (node (ref "U8") (pin "46") (pinfunction "AGND_46") (pintype "power_in"))
      (node (ref "U8") (pin "49") (pinfunction "EP_49") (pintype "passive"))
      (node (ref "Y1") (pin "2") (pinfunction "GND_2") (pintype "passive"))
    )
    (net (code "33") (name "MAX_IO0") (class "Default")
      (node (ref "S8") (pin "1B") (pinfunction "1B_1B") (pintype "passive"))
      (node (ref "U8") (pin "11") (pinfunction "GPIO0_11") (pintype "passive"))
    )
    (net (code "34") (name "MAX_IO1") (class "Default")
      (node (ref "S8") (pin "2B") (pinfunction "2B_2B") (pintype "passive"))
      (node (ref "U8") (pin "12") (pinfunction "GPIO1_12") (pintype "passive"))
    )
    (net (code "35") (name "MAX_IO2") (class "Default")
      (node (ref "S8") (pin "3B") (pinfunction "3B_3B") (pintype "passive"))
      (node (ref "U8") (pin "13") (pinfunction "GPIO2_13") (pintype "passive"))
    )
    (net (code "36") (name "MAX_IO3") (class "Default")
      (node (ref "S8") (pin "4B") (pinfunction "4B_4B") (pintype "passive"))
      (node (ref "U8") (pin "14") (pinfunction "GPIO3_14") (pintype "passive"))
    )
    (net (code "37") (name "MAX_IO4") (class "Default")
      (node (ref "S8") (pin "5B") (pinfunction "5B_5B") (pintype "passive"))
      (node (ref "U8") (pin "19") (pinfunction "GPIO4_19") (pintype "passive"))
    )
    (net (code "38") (name "MAX_IO5") (class "Default")
      (node (ref "S8") (pin "6B") (pinfunction "6B_6B") (pintype "passive"))
      (node (ref "U8") (pin "20") (pinfunction "GPIO5_20") (pintype "passive"))
    )
    (net (code "39") (name "MAX_IO6") (class "Default")
      (node (ref "S8") (pin "7B") (pinfunction "7B_7B") (pintype "passive"))
      (node (ref "U8") (pin "21") (pinfunction "GPIO6_21") (pintype "passive"))
    )
    (net (code "40") (name "MAX_IO7") (class "Default")
      (node (ref "S8") (pin "8B") (pinfunction "8B_8B") (pintype "passive"))
      (node (ref "U8") (pin "22") (pinfunction "GPIO7_22") (pintype "passive"))
    )
    (net (code "41") (name "MAX_IO8") (class "Default")
      (node (ref "CON1") (pin "6") (pinfunction "6_6") (pintype "passive"))
      (node (ref "U8") (pin "27") (pinfunction "GPIO8_27") (pintype "passive"))
    )
    (net (code "42") (name "MAX_IO9") (class "Default")
      (node (ref "CON1") (pin "8") (pinfunction "8_8") (pintype "passive"))
      (node (ref "U8") (pin "28") (pinfunction "GPIO9_28") (pintype "passive"))
    )
    (net (code "43") (name "MAX_IO10") (class "Default")
      (node (ref "CON1") (pin "10") (pinfunction "10_10") (pintype "passive"))
      (node (ref "U8") (pin "29") (pinfunction "GPIO10_29") (pintype "passive"))
    )
    (net (code "44") (name "MAX_IO11") (class "Default")
      (node (ref "CON1") (pin "12") (pinfunction "12_12") (pintype "passive"))
      (node (ref "U8") (pin "30") (pinfunction "GPIO11_30") (pintype "passive"))
    )
    (net (code "45") (name "MAX_IO12") (class "Default")
      (node (ref "CON1") (pin "11") (pinfunction "11_11") (pintype "passive"))
      (node (ref "U8") (pin "35") (pinfunction "GPIO12_35") (pintype "passive"))
    )
    (net (code "46") (name "MAX_IO13") (class "Default")
      (node (ref "CON1") (pin "9") (pinfunction "9_9") (pintype "passive"))
      (node (ref "U8") (pin "36") (pinfunction "GPIO13_36") (pintype "passive"))
    )
    (net (code "47") (name "MAX_IO14") (class "Default")
      (node (ref "CON1") (pin "7") (pinfunction "7_7") (pintype "passive"))
      (node (ref "U8") (pin "37") (pinfunction "GPIO14_37") (pintype "passive"))
    )
    (net (code "48") (name "MAX_IO15") (class "Default")
      (node (ref "CON1") (pin "5") (pinfunction "5_5") (pintype "passive"))
      (node (ref "U8") (pin "38") (pinfunction "GPIO15_38") (pintype "passive"))
    )
    (net (code "49") (name "Net-(C23-Pad2)") (class "Default")
      (node (ref "C23") (pin "2") (pinfunction "2_2") (pintype "passive"))
      (node (ref "R14") (pin "2") (pinfunction "2_2") (pintype "passive"))
      (node (ref "U$6") (pin "-") (pinfunction "-_-") (pintype "passive"))
    )
    (net (code "50") (name "Net-(C24-Pad2)") (class "Default")
      (node (ref "C24") (pin "2") (pinfunction "2_2") (pintype "passive"))
      (node (ref "C26") (pin "2") (pinfunction "2_2") (pintype "passive"))
      (node (ref "R15") (pin "2") (pinfunction "2_2") (pintype "passive"))
      (node (ref "R16") (pin "1") (pinfunction "1_1") (pintype "passive"))
      (node (ref "U$6") (pin "+") (pinfunction "+_+") (pintype "passive"))
    )
    (net (code "51") (name "Net-(C25-Pad2)") (class "Default")
      (node (ref "C25") (pin "2") (pinfunction "2_2") (pintype "passive"))
      (node (ref "C26") (pin "1") (pinfunction "1_1") (pintype "passive"))
      (node (ref "R15") (pin "1") (pinfunction "1_1") (pintype "passive"))
    )
    (net (code "52") (name "Net-(CON3-PWDN)") (class "Default")
      (node (ref "CON3") (pin "P$8") (pinfunction "PWDN_P$8") (pintype "input"))
      (node (ref "R3") (pin "2") (pinfunction "2_2") (pintype "passive"))
    )
    (net (code "53") (name "Net-(CON3-RESET)") (class "Default")
      (node (ref "C4") (pin "1") (pinfunction "1_1") (pintype "passive"))
      (node (ref "CON3") (pin "P$6") (pinfunction "RESET_P$6") (pintype "input"))
      (node (ref "R4") (pin "2") (pinfunction "2_2") (pintype "passive"))
    )
    (net (code "54") (name "Net-(L2-1)") (class "Default")
      (node (ref "C41") (pin "2") (pinfunction "2_2") (pintype "passive"))
      (node (ref "D5") (pin "C") (pinfunction "C_C") (pintype "passive"))
      (node (ref "L2") (pin "P$1") (pinfunction "1_P$1") (pintype "passive"))
      (node (ref "U12") (pin "8") (pinfunction "SW_8") (pintype "output"))
    )
    (net (code "55") (name "Net-(R2-Pad2)") (class "Default")
      (node (ref "R2") (pin "2") (pinfunction "2_2") (pintype "passive"))
      (node (ref "S2") (pin "3") (pinfunction "3_3") (pintype "passive"))
      (node (ref "S2") (pin "4") (pinfunction "4_4") (pintype "passive"))
    )
    (net (code "56") (name "Net-(R5-Pad2)") (class "Default")
      (node (ref "R5") (pin "2") (pinfunction "2_2") (pintype "passive"))
      (node (ref "R6") (pin "1") (pinfunction "1_1") (pintype "passive"))
    )
    (net (code "57") (name "Net-(SPR1-1)") (class "Default")
      (node (ref "SPR1") (pin "+") (pinfunction "1_+") (pintype "passive"))
      (node (ref "U14") (pin "17") (pinfunction "SPKOUTP_17") (pintype "output"))
    )
    (net (code "58") (name "Net-(SPR1-2)") (class "Default")
      (node (ref "SPR1") (pin "-") (pinfunction "2_-") (pintype "passive"))
      (node (ref "U14") (pin "19") (pinfunction "SPKOUTN_19") (pintype "output"))
    )
    (net (code "59") (name "Net-(U1-DVI)") (class "Default")
      (node (ref "C28") (pin "1") (pinfunction "1_1") (pintype "passive"))
      (node (ref "R17") (pin "1") (pinfunction "1_1") (pintype "passive"))
      (node (ref "U1") (pin "5") (pinfunction "DVI_5") (pintype "input"))
    )
    (net (code "60") (name "Net-(U3-PWM)") (class "Default")
      (node (ref "U3") (pin "4") (pinfunction "PWM_4") (pintype "output"))
      (node (ref "U3") (pin "5") (pinfunction "SENSE_5") (pintype "input"))
    )
    (net (code "61") (name "Net-(U3-~{RESET})") (class "Default")
      (node (ref "R30") (pin "1") (pinfunction "1_1") (pintype "passive"))
      (node (ref "U3") (pin "2") (pinfunction "~{RESET}_2") (pintype "input"))
    )
    (net (code "62") (name "Net-(U4-D)") (class "Default")
      (node (ref "U4") (pin "4") (pinfunction "D_4") (pintype "input"))
      (node (ref "U8") (pin "42") (pinfunction "TX3_42") (pintype "passive"))
    )
    (net (code "63") (name "Net-(U4-DE)") (class "Default")
      (node (ref "U4") (pin "2") (pinfunction "~{RE}_2") (pintype "input"))
      (node (ref "U4") (pin "3") (pinfunction "DE_3") (pintype "input"))
      (node (ref "U8") (pin "39") (pinfunction "*RTS3_39") (pintype "passive"))
    )
    (net (code "64") (name "Net-(U4-R)") (class "Default")
      (node (ref "U4") (pin "1") (pinfunction "R_1") (pintype "output"))
      (node (ref "U8") (pin "41") (pinfunction "RX3_41") (pintype "passive"))
    )
    (net (code "65") (name "Net-(U5-D)") (class "Default")
      (node (ref "U5") (pin "4") (pinfunction "D_4") (pintype "input"))
      (node (ref "U8") (pin "34") (pinfunction "TX2_34") (pintype "passive"))
    )
    (net (code "66") (name "Net-(U5-DE)") (class "Default")
      (node (ref "U5") (pin "2") (pinfunction "~{RE}_2") (pintype "input"))
      (node (ref "U5") (pin "3") (pinfunction "DE_3") (pintype "input"))
      (node (ref "U8") (pin "31") (pinfunction "*RTS2_31") (pintype "passive"))
    )
    (net (code "67") (name "Net-(U5-R)") (class "Default")
      (node (ref "U5") (pin "1") (pinfunction "R_1") (pintype "output"))
      (node (ref "U8") (pin "33") (pinfunction "RX2_33") (pintype "passive"))
    )
    (net (code "68") (name "Net-(U6-D)") (class "Default")
      (node (ref "U6") (pin "4") (pinfunction "D_4") (pintype "input"))
      (node (ref "U8") (pin "26") (pinfunction "TX1_26") (pintype "passive"))
    )
    (net (code "69") (name "Net-(U6-DE)") (class "Default")
      (node (ref "U6") (pin "2") (pinfunction "~{RE}_2") (pintype "input"))
      (node (ref "U6") (pin "3") (pinfunction "DE_3") (pintype "input"))
      (node (ref "U8") (pin "23") (pinfunction "*RTS1_23") (pintype "passive"))
    )
    (net (code "70") (name "Net-(U6-R)") (class "Default")
      (node (ref "U6") (pin "1") (pinfunction "R_1") (pintype "output"))
      (node (ref "U8") (pin "25") (pinfunction "RX1_25") (pintype "passive"))
    )
    (net (code "71") (name "Net-(U7-D)") (class "Default")
      (node (ref "U7") (pin "4") (pinfunction "D_4") (pintype "input"))
      (node (ref "U8") (pin "18") (pinfunction "TX0_18") (pintype "passive"))
    )
    (net (code "72") (name "Net-(U7-DE)") (class "Default")
      (node (ref "U7") (pin "2") (pinfunction "~{RE}_2") (pintype "input"))
      (node (ref "U7") (pin "3") (pinfunction "DE_3") (pintype "input"))
      (node (ref "U8") (pin "15") (pinfunction "*RTS0_15") (pintype "passive"))
    )
    (net (code "73") (name "Net-(U7-R)") (class "Default")
      (node (ref "U7") (pin "1") (pinfunction "R_1") (pintype "output"))
      (node (ref "U8") (pin "17") (pinfunction "RX0_17") (pintype "passive"))
    )
    (net (code "74") (name "Net-(U8-*RST)") (class "Default")
      (node (ref "C13") (pin "1") (pinfunction "1_1") (pintype "passive"))
      (node (ref "R12") (pin "2") (pinfunction "2_2") (pintype "passive"))
      (node (ref "U8") (pin "8") (pinfunction "*RST_8") (pintype "passive"))
    )
    (net (code "75") (name "Net-(U8-V18)") (class "Default")
      (node (ref "C14") (pin "1") (pinfunction "1_1") (pintype "passive"))
      (node (ref "U8") (pin "48") (pinfunction "V18_48") (pintype "power_in"))
    )
    (net (code "76") (name "Net-(U12-BOOT)") (class "Default")
      (node (ref "C41") (pin "1") (pinfunction "1_1") (pintype "passive"))
      (node (ref "U12") (pin "1") (pinfunction "BOOT_1") (pintype "power_in"))
    )
    (net (code "77") (name "Net-(U12-FB)") (class "Default")
      (node (ref "C37") (pin "2") (pinfunction "2_2") (pintype "passive"))
      (node (ref "R34") (pin "1") (pinfunction "1_1") (pintype "passive"))
      (node (ref "R35") (pin "2") (pinfunction "2_2") (pintype "passive"))
      (node (ref "R36") (pin "2") (pinfunction "2_2") (pintype "passive"))
      (node (ref "U12") (pin "5") (pinfunction "FB_5") (pintype "input"))
    )
    (net (code "78") (name "Net-(U12-RT{slash}SYNC)") (class "Default")
      (node (ref "R33") (pin "1") (pinfunction "1_1") (pintype "passive"))
      (node (ref "U12") (pin "4") (pinfunction "RT/SYNC_4") (pintype "input"))
    )
    (net (code "79") (name "Net-(U14-MICBIAS)") (class "Default")
      (node (ref "C25") (pin "1") (pinfunction "1_1") (pintype "passive"))
      (node (ref "R16") (pin "2") (pinfunction "2_2") (pintype "passive"))
      (node (ref "U14") (pin "1") (pinfunction "MICBIAS_1") (pintype "output"))
    )
    (net (code "80") (name "Net-(U14-MICN)") (class "Default")
      (node (ref "C23") (pin "1") (pinfunction "1_1") (pintype "passive"))
      (node (ref "U14") (pin "23") (pinfunction "MICN_23") (pintype "input"))
    )
    (net (code "81") (name "Net-(U14-MICP)") (class "Default")
      (node (ref "C24") (pin "1") (pinfunction "1_1") (pintype "passive"))
      (node (ref "U14") (pin "24") (pinfunction "MICP_24") (pintype "input"))
    )
    (net (code "82") (name "Net-(U14-SPKVDD)") (class "Default")
      (node (ref "C21") (pin "2") (pinfunction "2_2") (pintype "passive"))
      (node (ref "R31") (pin "2") (pinfunction "2_2") (pintype "passive"))
      (node (ref "U14") (pin "20") (pinfunction "SPKVDD_20") (pintype "power_in"))
    )
    (net (code "83") (name "Net-(U14-VMID)") (class "Default")
      (node (ref "C22") (pin "2") (pinfunction "2_2") (pintype "passive"))
      (node (ref "U14") (pin "22") (pinfunction "VMID_22") (pintype "bidirectional"))
    )
    (net (code "84") (name "Net-(U18-FB)") (class "Default")
      (node (ref "R5") (pin "1") (pinfunction "1_1") (pintype "passive"))
      (node (ref "R7") (pin "2") (pinfunction "2_2") (pintype "passive"))
      (node (ref "U18") (pin "4") (pinfunction "FB_4") (pintype "power_in"))
    )
    (net (code "85") (name "RS485_A0") (class "Default")
      (node (ref "CON2") (pin "1") (pinfunction "1_1") (pintype "passive"))
      (node (ref "D1") (pin "2") (pinfunction "IO2_2") (pintype "bidirectional"))
      (node (ref "R18") (pin "2") (pinfunction "2_2") (pintype "passive"))
      (node (ref "R19") (pin "1") (pinfunction "1_1") (pintype "passive"))
      (node (ref "U7") (pin "6") (pinfunction "A_6") (pintype "output"))
    )
    (net (code "86") (name "RS485_A1") (class "Default")
      (node (ref "CON2") (pin "3") (pinfunction "3_3") (pintype "passive"))
      (node (ref "D2") (pin "2") (pinfunction "IO2_2") (pintype "bidirectional"))
      (node (ref "R21") (pin "2") (pinfunction "2_2") (pintype "passive"))
      (node (ref "R22") (pin "1") (pinfunction "1_1") (pintype "passive"))
      (node (ref "U6") (pin "6") (pinfunction "A_6") (pintype "output"))
    )
    (net (code "87") (name "RS485_A2") (class "Default")
      (node (ref "CON2") (pin "5") (pinfunction "5_5") (pintype "passive"))
      (node (ref "D3") (pin "2") (pinfunction "IO2_2") (pintype "bidirectional"))
      (node (ref "R24") (pin "2") (pinfunction "2_2") (pintype "passive"))
      (node (ref "R25") (pin "1") (pinfunction "1_1") (pintype "passive"))
      (node (ref "U5") (pin "6") (pinfunction "A_6") (pintype "output"))
    )
    (net (code "88") (name "RS485_A3") (class "Default")
      (node (ref "CON2") (pin "7") (pinfunction "7_7") (pintype "passive"))
      (node (ref "D4") (pin "2") (pinfunction "IO2_2") (pintype "bidirectional"))
      (node (ref "R27") (pin "2") (pinfunction "2_2") (pintype "passive"))
      (node (ref "R28") (pin "1") (pinfunction "1_1") (pintype "passive"))
      (node (ref "U4") (pin "6") (pinfunction "A_6") (pintype "output"))
    )
    (net (code "89") (name "RS485_B0") (class "Default")
      (node (ref "CON2") (pin "2") (pinfunction "2_2") (pintype "passive"))
      (node (ref "D1") (pin "1") (pinfunction "IO1_1") (pintype "bidirectional"))
      (node (ref "R19") (pin "2") (pinfunction "2_2") (pintype "passive"))
      (node (ref "R20") (pin "1") (pinfunction "1_1") (pintype "passive"))
      (node (ref "U7") (pin "7") (pinfunction "B_7") (pintype "output"))
    )
    (net (code "90") (name "RS485_B1") (class "Default")
      (node (ref "CON2") (pin "4") (pinfunction "4_4") (pintype "passive"))
      (node (ref "D2") (pin "1") (pinfunction "IO1_1") (pintype "bidirectional"))
      (node (ref "R22") (pin "2") (pinfunction "2_2") (pintype "passive"))
      (node (ref "R23") (pin "1") (pinfunction "1_1") (pintype "passive"))
      (node (ref "U6") (pin "7") (pinfunction "B_7") (pintype "output"))
    )
    (net (code "91") (name "RS485_B2") (class "Default")
      (node (ref "CON2") (pin "6") (pinfunction "6_6") (pintype "passive"))
      (node (ref "D3") (pin "1") (pinfunction "IO1_1") (pintype "bidirectional"))
      (node (ref "R25") (pin "2") (pinfunction "2_2") (pintype "passive"))
      (node (ref "R26") (pin "1") (pinfunction "1_1") (pintype "passive"))
      (node (ref "U5") (pin "7") (pinfunction "B_7") (pintype "output"))
    )
    (net (code "92") (name "RS485_B3") (class "Default")
      (node (ref "CON2") (pin "8") (pinfunction "8_8") (pintype "passive"))
      (node (ref "D4") (pin "1") (pinfunction "IO1_1") (pintype "bidirectional"))
      (node (ref "R28") (pin "2") (pinfunction "2_2") (pintype "passive"))
      (node (ref "R29") (pin "1") (pinfunction "1_1") (pintype "passive"))
      (node (ref "U4") (pin "7") (pinfunction "B_7") (pintype "output"))
    )
    (net (code "93") (name "unconnected-(A1-SCK{slash}CLK-Pad20)") (class "Default")
      (node (ref "A1") (pin "20") (pinfunction "SCK/CLK_20") (pintype "bidirectional"))
    )
    (net (code "94") (name "unconnected-(A1-SCS{slash}CMD-Pad19)") (class "Default")
      (node (ref "A1") (pin "19") (pinfunction "SCS/CMD_19") (pintype "bidirectional"))
    )
    (net (code "95") (name "unconnected-(A1-SDI{slash}SD1-Pad22)") (class "Default")
      (node (ref "A1") (pin "22") (pinfunction "SDI/SD1_22") (pintype "bidirectional"))
    )
    (net (code "96") (name "unconnected-(A1-SDO{slash}SD0-Pad21)") (class "Default")
      (node (ref "A1") (pin "21") (pinfunction "SDO/SD0_21") (pintype "bidirectional"))
    )
    (net (code "97") (name "unconnected-(A1-SHD{slash}SD2-Pad17)") (class "Default")
      (node (ref "A1") (pin "17") (pinfunction "SHD/SD2_17") (pintype "bidirectional"))
    )
    (net (code "98") (name "unconnected-(A1-SWP{slash}SD3-Pad18)") (class "Default")
      (node (ref "A1") (pin "18") (pinfunction "SWP/SD3_18") (pintype "bidirectional"))
    )
    (net (code "99") (name "unconnected-(CON3-STROBE-PadP$1)") (class "Default")
      (node (ref "CON3") (pin "P$1") (pinfunction "STROBE_P$1") (pintype "output"))
    )
    (net (code "100") (name "unconnected-(CON3-Y0-PadP$24)") (class "Default")
      (node (ref "CON3") (pin "P$24") (pinfunction "Y0_P$24") (pintype "output"))
    )
    (net (code "101") (name "unconnected-(CON3-Y1-PadP$23)") (class "Default")
      (node (ref "CON3") (pin "P$23") (pinfunction "Y1_P$23") (pintype "output"))
    )
    (net (code "102") (name "unconnected-(U3-~{INT}-Pad3)") (class "Default")
      (node (ref "U3") (pin "3") (pinfunction "~{INT}_3") (pintype "output"))
    )
    (net (code "103") (name "unconnected-(U8-*CTS1-Pad24)") (class "Default")
      (node (ref "U8") (pin "24") (pinfunction "*CTS1_24") (pintype "passive"))
    )
    (net (code "104") (name "unconnected-(U8-*CTS2-Pad32)") (class "Default")
      (node (ref "U8") (pin "32") (pinfunction "*CTS2_32") (pintype "passive"))
    )
    (net (code "105") (name "unconnected-(U8-*CTS3-Pad40)") (class "Default")
      (node (ref "U8") (pin "40") (pinfunction "*CTS3_40") (pintype "passive"))
    )
    (net (code "106") (name "unconnected-(U8-XOUT-Pad44)") (class "Default")
      (node (ref "U8") (pin "44") (pinfunction "XOUT_44") (pintype "passive"))
    )
    (net (code "107") (name "unconnected-(U12-PGOOD-Pad6)") (class "Default")
      (node (ref "U12") (pin "6") (pinfunction "PGOOD_6") (pintype "output"))
    )
    (net (code "108") (name "unconnected-(U14-AUX-Pad21)") (class "Default")
      (node (ref "U14") (pin "21") (pinfunction "AUX_21") (pintype "input"))
    )
    (net (code "109") (name "unconnected-(U14-CSB{slash}GPIO-Pad12)") (class "Default")
      (node (ref "U14") (pin "12") (pinfunction "CSB/GPIO_12") (pintype "bidirectional"))
    )
    (net (code "110") (name "unconnected-(U14-MONOOUT-Pad16)") (class "Default")
      (node (ref "U14") (pin "16") (pinfunction "MONOOUT_16") (pintype "output"))
    )
    (net (code "111") (name "unconnected-(Y1-~{ST}-Pad1)") (class "Default")
      (node (ref "Y1") (pin "1") (pinfunction "~{ST}_1") (pintype "input"))
    )
  )
)
